# kiwi-basic.net
KiCad netlist of a schematic drawn in EAGLE
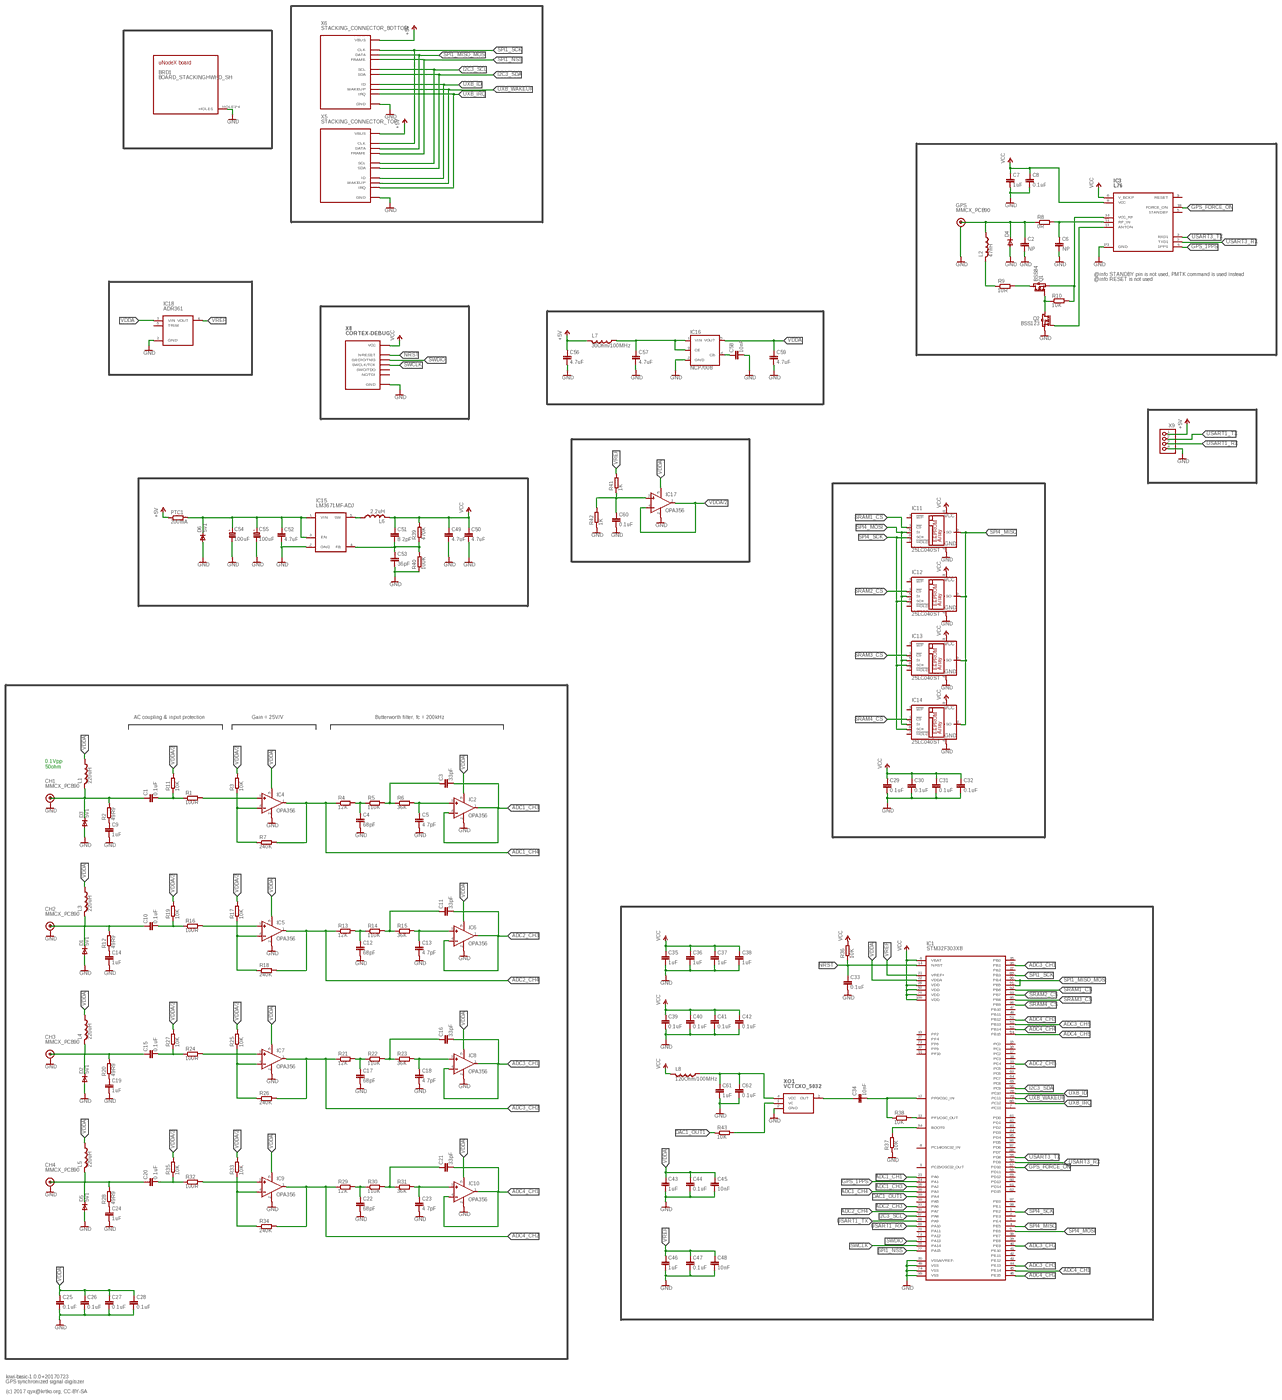
[diagram p0: schematic, sheet 1, overview]
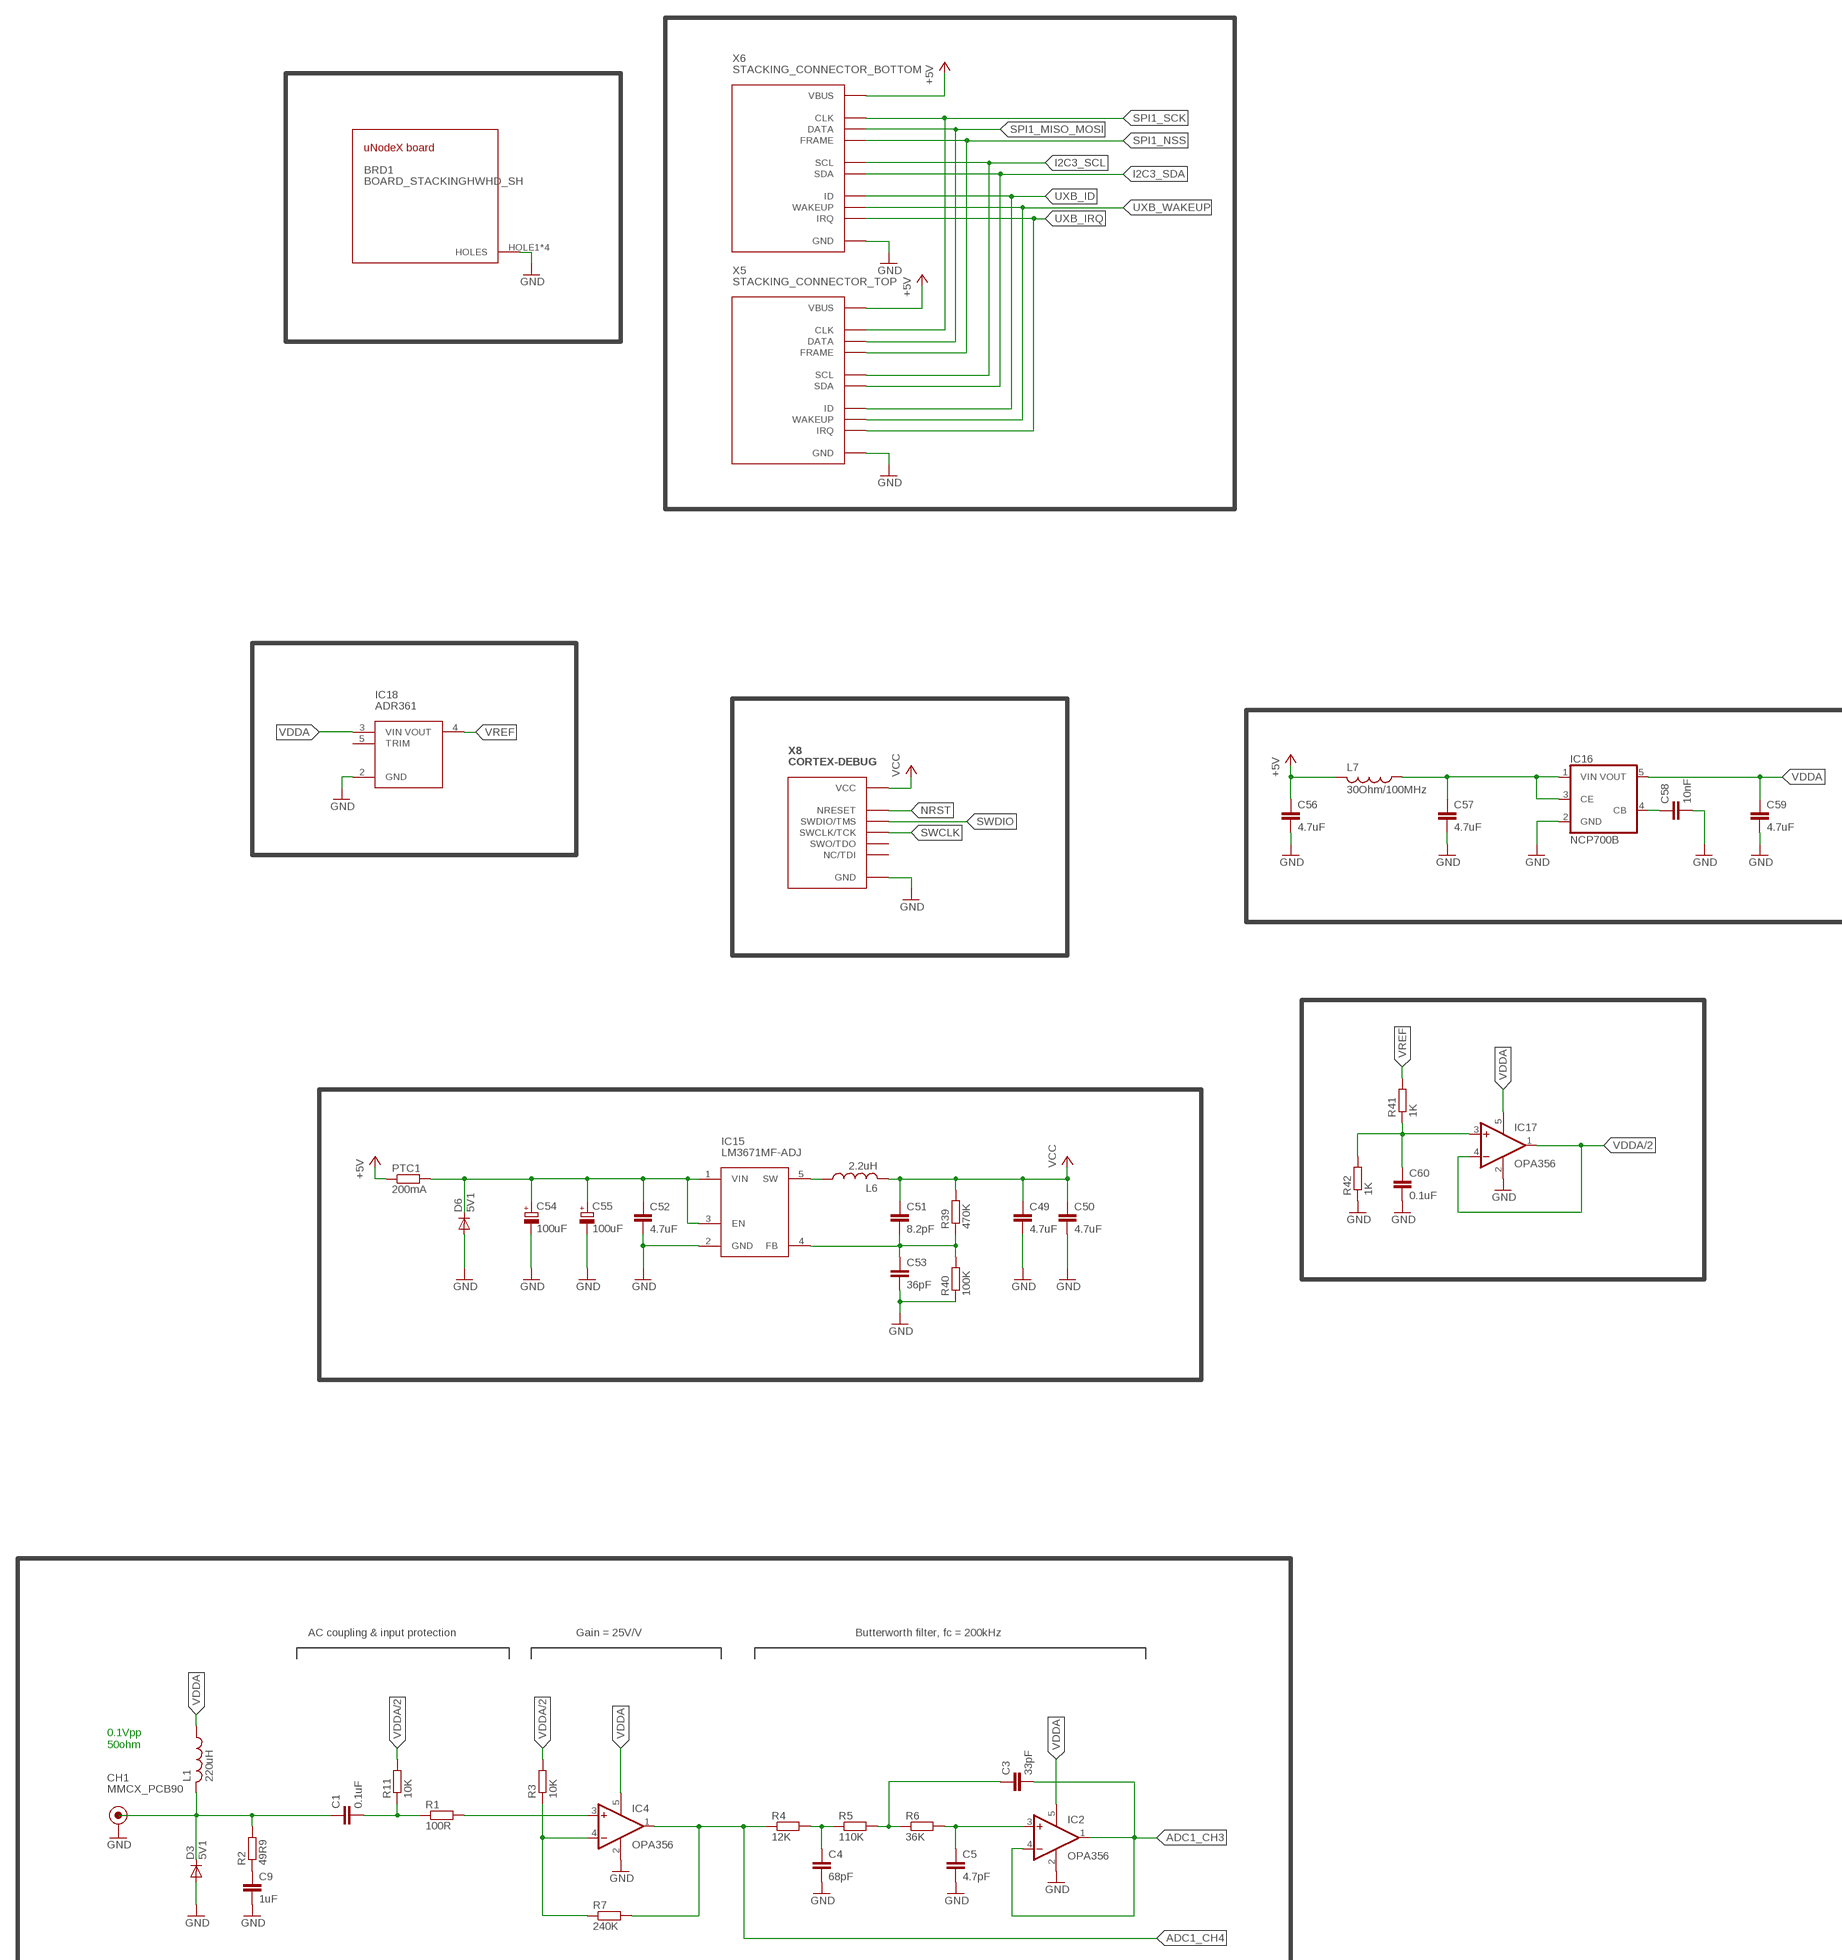
[diagram p1: schematic, sheet 1, part 1 of 4]
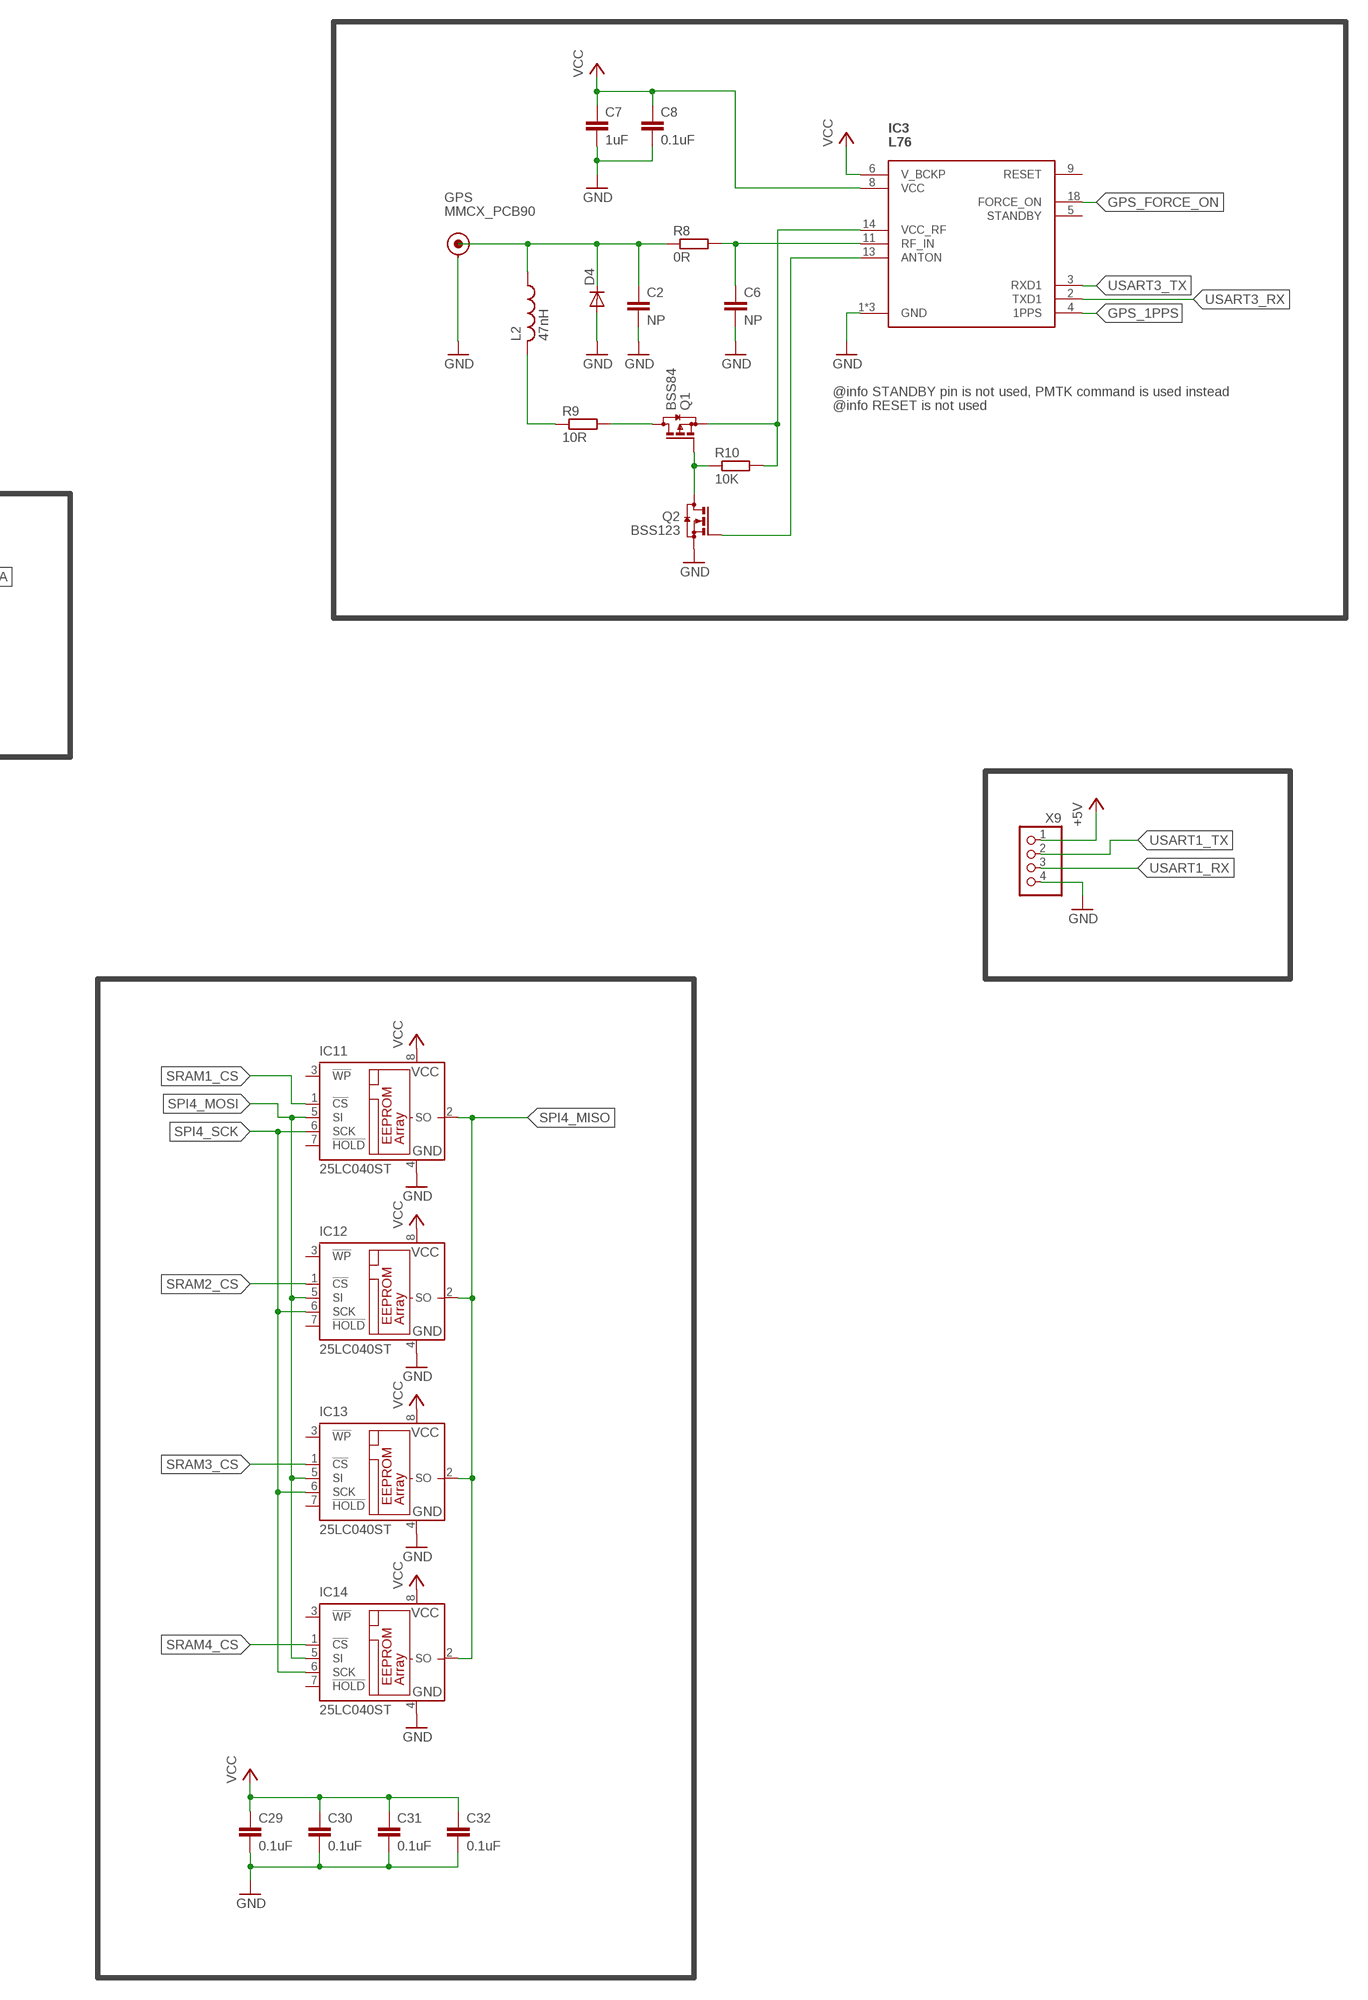
[diagram p2: schematic, sheet 1, part 2 of 4]
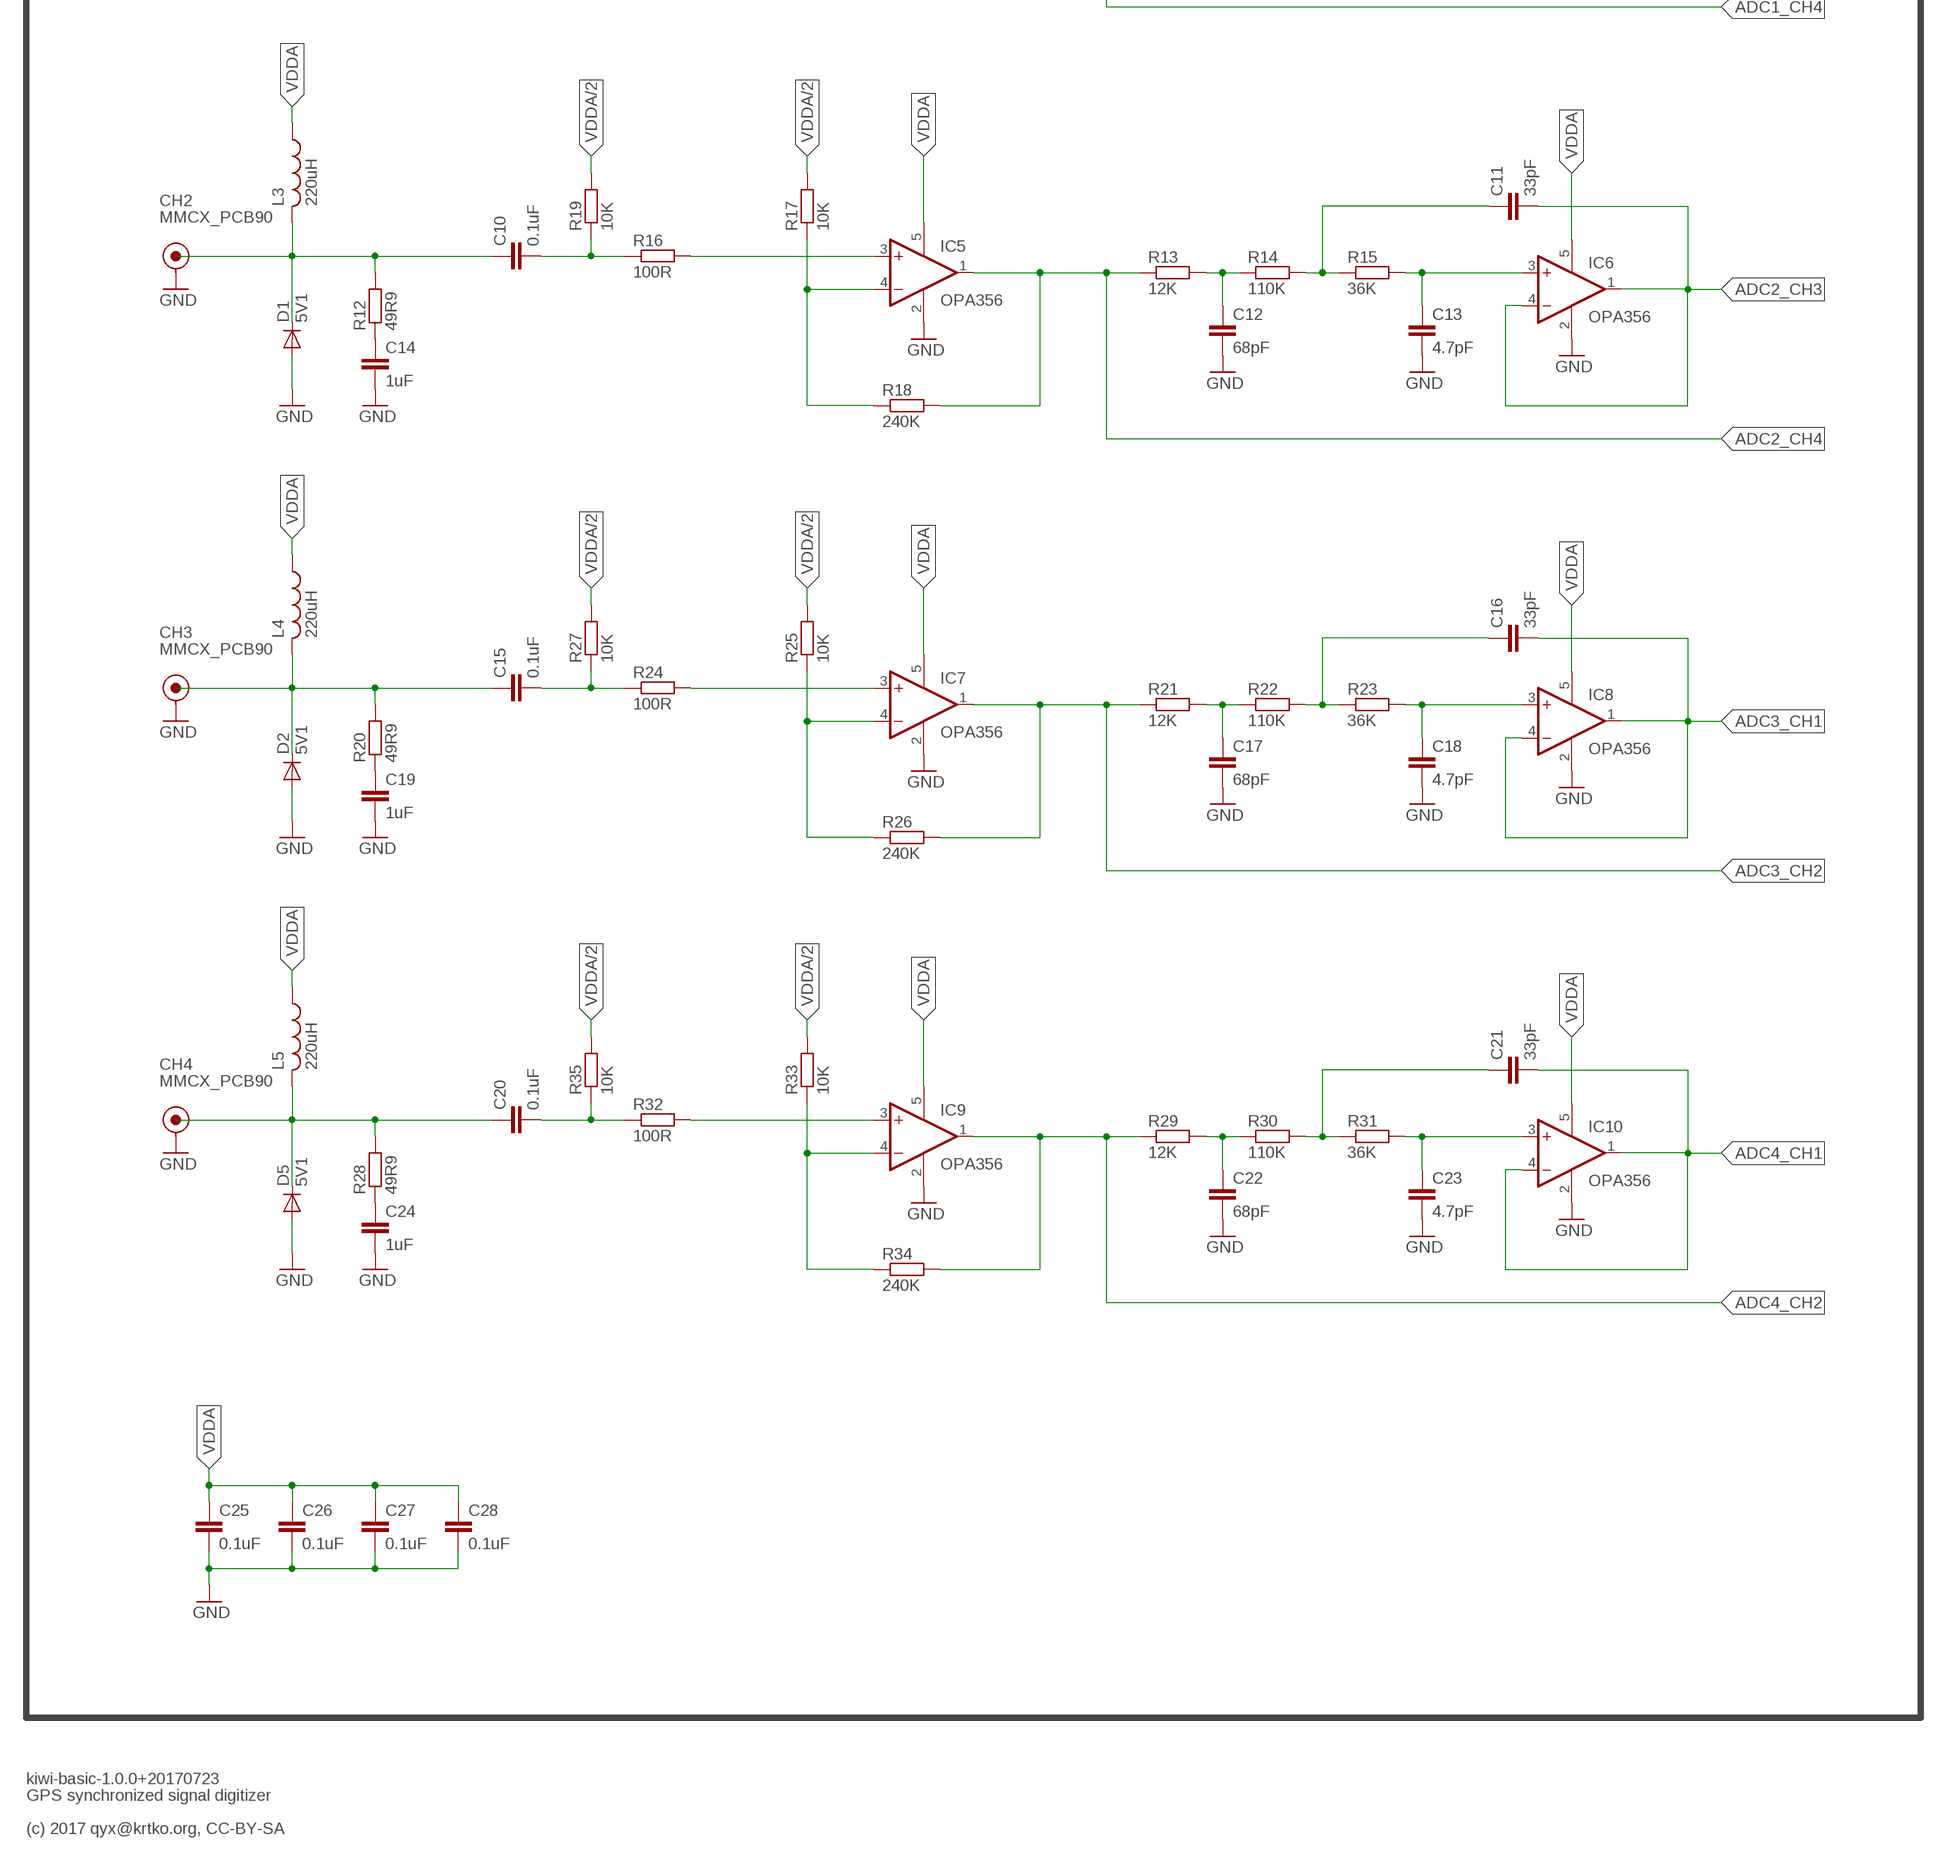
[diagram p3: schematic, sheet 1, part 3 of 4]
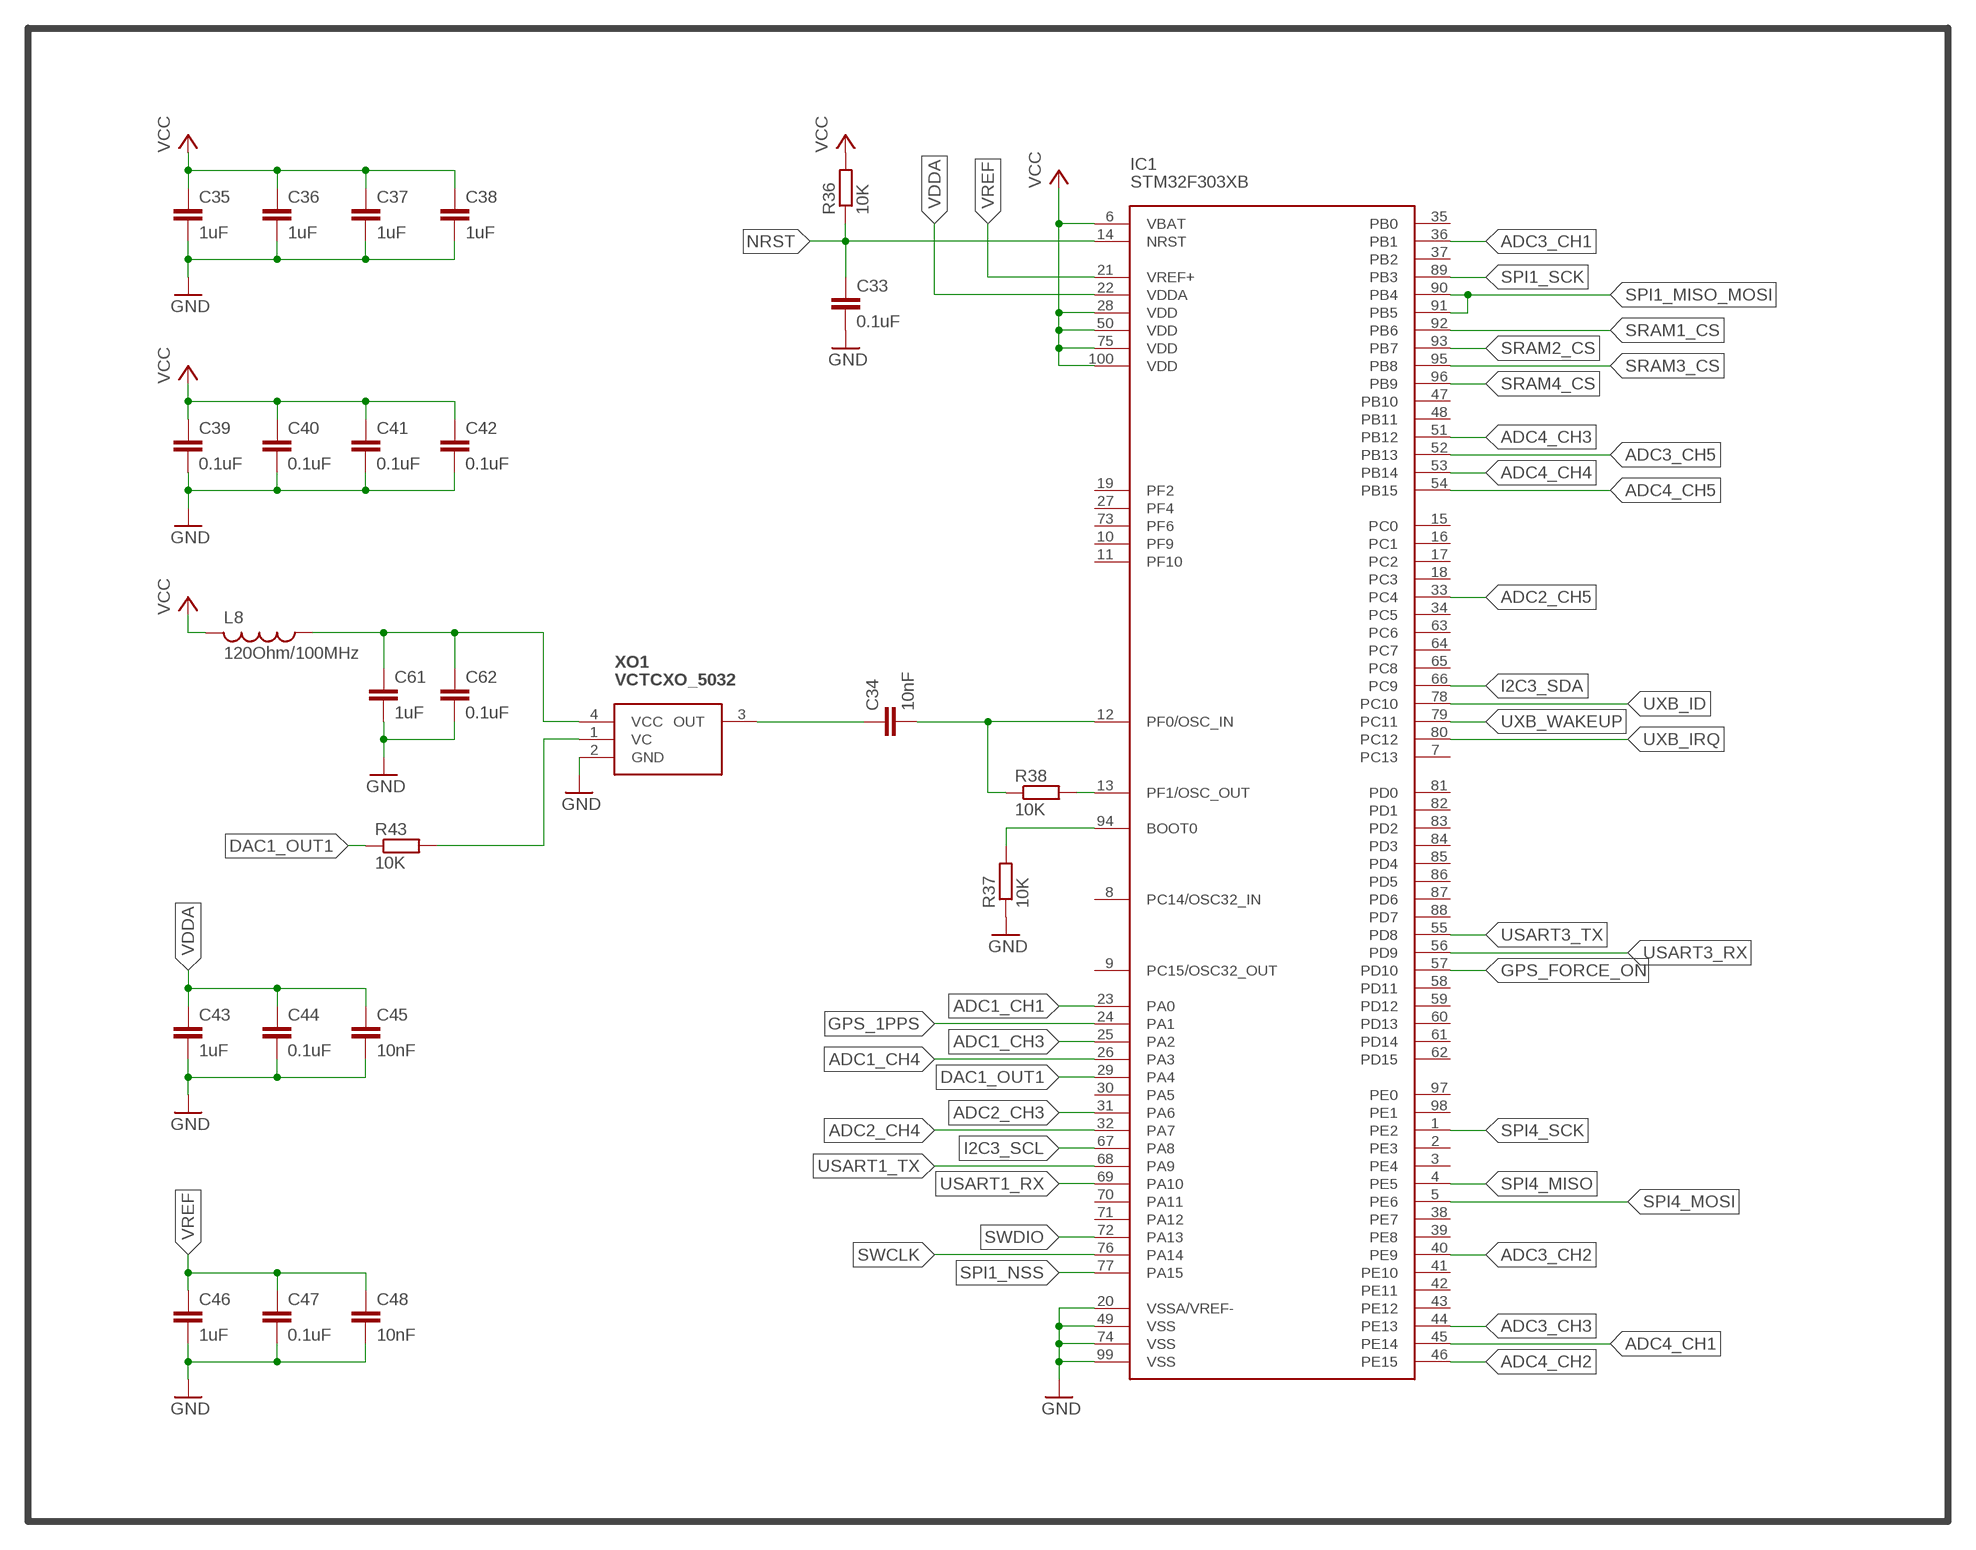
[diagram p4: schematic, sheet 1, part 4 of 4]

(export (version "E")
  (design (tool "Eeschema 10.0.6"))
  (components
    (comp (ref "BRD1")
      (value "BOARD_STACKINGHWHD_SH")
      (footprint "eagle-import:HWHD_SHARP_CORNERS")
      (libsource (lib "eagle-import") (part "BOARD_STACKINGHWHD_SH"))
    )
    (comp (ref "C1")
      (value "0.1uF")
      (footprint "eagle-import:C0603")
      (libsource (lib "eagle-import") (part "C-EUC0603"))
    )
    (comp (ref "C2")
      (value "NP")
      (footprint "eagle-import:C0603")
      (libsource (lib "eagle-import") (part "C-EUC0603"))
    )
    (comp (ref "C3")
      (value "33pF")
      (footprint "eagle-import:C0603")
      (libsource (lib "eagle-import") (part "C-EUC0603"))
    )
    (comp (ref "C4")
      (value "68pF")
      (footprint "eagle-import:C0603")
      (libsource (lib "eagle-import") (part "C-EUC0603"))
    )
    (comp (ref "C5")
      (value "4.7pF")
      (footprint "eagle-import:C0603")
      (libsource (lib "eagle-import") (part "C-EUC0603"))
    )
    (comp (ref "C6")
      (value "NP")
      (footprint "eagle-import:C0603")
      (libsource (lib "eagle-import") (part "C-EUC0603"))
    )
    (comp (ref "C7")
      (value "1uF")
      (footprint "eagle-import:C0603")
      (libsource (lib "eagle-import") (part "C-EUC0603"))
    )
    (comp (ref "C8")
      (value "0.1uF")
      (footprint "eagle-import:C0603")
      (libsource (lib "eagle-import") (part "C-EUC0603"))
    )
    (comp (ref "C9")
      (value "1uF")
      (footprint "eagle-import:C0603")
      (libsource (lib "eagle-import") (part "C-EUC0603"))
    )
    (comp (ref "C10")
      (value "0.1uF")
      (footprint "eagle-import:C0603")
      (libsource (lib "eagle-import") (part "C-EUC0603"))
    )
    (comp (ref "C11")
      (value "33pF")
      (footprint "eagle-import:C0603")
      (libsource (lib "eagle-import") (part "C-EUC0603"))
    )
    (comp (ref "C12")
      (value "68pF")
      (footprint "eagle-import:C0603")
      (libsource (lib "eagle-import") (part "C-EUC0603"))
    )
    (comp (ref "C13")
      (value "4.7pF")
      (footprint "eagle-import:C0603")
      (libsource (lib "eagle-import") (part "C-EUC0603"))
    )
    (comp (ref "C14")
      (value "1uF")
      (footprint "eagle-import:C0603")
      (libsource (lib "eagle-import") (part "C-EUC0603"))
    )
    (comp (ref "C15")
      (value "0.1uF")
      (footprint "eagle-import:C0603")
      (libsource (lib "eagle-import") (part "C-EUC0603"))
    )
    (comp (ref "C16")
      (value "33pF")
      (footprint "eagle-import:C0603")
      (libsource (lib "eagle-import") (part "C-EUC0603"))
    )
    (comp (ref "C17")
      (value "68pF")
      (footprint "eagle-import:C0603")
      (libsource (lib "eagle-import") (part "C-EUC0603"))
    )
    (comp (ref "C18")
      (value "4.7pF")
      (footprint "eagle-import:C0603")
      (libsource (lib "eagle-import") (part "C-EUC0603"))
    )
    (comp (ref "C19")
      (value "1uF")
      (footprint "eagle-import:C0603")
      (libsource (lib "eagle-import") (part "C-EUC0603"))
    )
    (comp (ref "C20")
      (value "0.1uF")
      (footprint "eagle-import:C0603")
      (libsource (lib "eagle-import") (part "C-EUC0603"))
    )
    (comp (ref "C21")
      (value "33pF")
      (footprint "eagle-import:C0603")
      (libsource (lib "eagle-import") (part "C-EUC0603"))
    )
    (comp (ref "C22")
      (value "68pF")
      (footprint "eagle-import:C0603")
      (libsource (lib "eagle-import") (part "C-EUC0603"))
    )
    (comp (ref "C23")
      (value "4.7pF")
      (footprint "eagle-import:C0603")
      (libsource (lib "eagle-import") (part "C-EUC0603"))
    )
    (comp (ref "C24")
      (value "1uF")
      (footprint "eagle-import:C0603")
      (libsource (lib "eagle-import") (part "C-EUC0603"))
    )
    (comp (ref "C25")
      (value "0.1uF")
      (footprint "eagle-import:C0603")
      (libsource (lib "eagle-import") (part "C-EUC0603"))
    )
    (comp (ref "C26")
      (value "0.1uF")
      (footprint "eagle-import:C0603")
      (libsource (lib "eagle-import") (part "C-EUC0603"))
    )
    (comp (ref "C27")
      (value "0.1uF")
      (footprint "eagle-import:C0603")
      (libsource (lib "eagle-import") (part "C-EUC0603"))
    )
    (comp (ref "C28")
      (value "0.1uF")
      (footprint "eagle-import:C0603")
      (libsource (lib "eagle-import") (part "C-EUC0603"))
    )
    (comp (ref "C29")
      (value "0.1uF")
      (footprint "eagle-import:C0603")
      (libsource (lib "eagle-import") (part "C-EUC0603"))
    )
    (comp (ref "C30")
      (value "0.1uF")
      (footprint "eagle-import:C0603")
      (libsource (lib "eagle-import") (part "C-EUC0603"))
    )
    (comp (ref "C31")
      (value "0.1uF")
      (footprint "eagle-import:C0603")
      (libsource (lib "eagle-import") (part "C-EUC0603"))
    )
    (comp (ref "C32")
      (value "0.1uF")
      (footprint "eagle-import:C0603")
      (libsource (lib "eagle-import") (part "C-EUC0603"))
    )
    (comp (ref "C33")
      (value "0.1uF")
      (footprint "eagle-import:C0603")
      (libsource (lib "eagle-import") (part "C-EUC0603"))
    )
    (comp (ref "C34")
      (value "10nF")
      (footprint "eagle-import:C0603")
      (libsource (lib "eagle-import") (part "C-EUC0603"))
    )
    (comp (ref "C35")
      (value "1uF")
      (footprint "eagle-import:C0603")
      (libsource (lib "eagle-import") (part "C-EUC0603"))
    )
    (comp (ref "C36")
      (value "1uF")
      (footprint "eagle-import:C0603")
      (libsource (lib "eagle-import") (part "C-EUC0603"))
    )
    (comp (ref "C37")
      (value "1uF")
      (footprint "eagle-import:C0603")
      (libsource (lib "eagle-import") (part "C-EUC0603"))
    )
    (comp (ref "C38")
      (value "1uF")
      (footprint "eagle-import:C0603")
      (libsource (lib "eagle-import") (part "C-EUC0603"))
    )
    (comp (ref "C39")
      (value "0.1uF")
      (footprint "eagle-import:C0603")
      (libsource (lib "eagle-import") (part "C-EUC0603"))
    )
    (comp (ref "C40")
      (value "0.1uF")
      (footprint "eagle-import:C0603")
      (libsource (lib "eagle-import") (part "C-EUC0603"))
    )
    (comp (ref "C41")
      (value "0.1uF")
      (footprint "eagle-import:C0603")
      (libsource (lib "eagle-import") (part "C-EUC0603"))
    )
    (comp (ref "C42")
      (value "0.1uF")
      (footprint "eagle-import:C0603")
      (libsource (lib "eagle-import") (part "C-EUC0603"))
    )
    (comp (ref "C43")
      (value "1uF")
      (footprint "eagle-import:C0603")
      (libsource (lib "eagle-import") (part "C-EUC0603"))
    )
    (comp (ref "C44")
      (value "0.1uF")
      (footprint "eagle-import:C0603")
      (libsource (lib "eagle-import") (part "C-EUC0603"))
    )
    (comp (ref "C45")
      (value "10nF")
      (footprint "eagle-import:C0603")
      (libsource (lib "eagle-import") (part "C-EUC0603"))
    )
    (comp (ref "C46")
      (value "1uF")
      (footprint "eagle-import:C0603")
      (libsource (lib "eagle-import") (part "C-EUC0603"))
    )
    (comp (ref "C47")
      (value "0.1uF")
      (footprint "eagle-import:C0603")
      (libsource (lib "eagle-import") (part "C-EUC0603"))
    )
    (comp (ref "C48")
      (value "10nF")
      (footprint "eagle-import:C0603")
      (libsource (lib "eagle-import") (part "C-EUC0603"))
    )
    (comp (ref "C49")
      (value "4.7uF")
      (footprint "eagle-import:C0805")
      (libsource (lib "eagle-import") (part "C-EUC0805"))
    )
    (comp (ref "C50")
      (value "4.7uF")
      (footprint "eagle-import:C0805")
      (libsource (lib "eagle-import") (part "C-EUC0805"))
    )
    (comp (ref "C51")
      (value "8.2pF")
      (footprint "eagle-import:C0603")
      (libsource (lib "eagle-import") (part "C-EUC0603"))
    )
    (comp (ref "C52")
      (value "4.7uF")
      (footprint "eagle-import:C0805")
      (libsource (lib "eagle-import") (part "C-EUC0805"))
    )
    (comp (ref "C53")
      (value "36pF")
      (footprint "eagle-import:C0603")
      (libsource (lib "eagle-import") (part "C-EUC0603"))
    )
    (comp (ref "C54")
      (value "100uF")
      (footprint "eagle-import:PANASONIC_D")
      (libsource (lib "eagle-import") (part "CPOL-EUD"))
    )
    (comp (ref "C55")
      (value "100uF")
      (footprint "eagle-import:PANASONIC_D")
      (libsource (lib "eagle-import") (part "CPOL-EUD"))
    )
    (comp (ref "C56")
      (value "4.7uF")
      (footprint "eagle-import:C0805")
      (libsource (lib "eagle-import") (part "C-EUC0805"))
    )
    (comp (ref "C57")
      (value "4.7uF")
      (footprint "eagle-import:C0805")
      (libsource (lib "eagle-import") (part "C-EUC0805"))
    )
    (comp (ref "C58")
      (value "10nF")
      (footprint "eagle-import:C0603")
      (libsource (lib "eagle-import") (part "C-EUC0603"))
    )
    (comp (ref "C59")
      (value "4.7uF")
      (footprint "eagle-import:C0805")
      (libsource (lib "eagle-import") (part "C-EUC0805"))
    )
    (comp (ref "C60")
      (value "0.1uF")
      (footprint "eagle-import:C0603")
      (libsource (lib "eagle-import") (part "C-EUC0603"))
    )
    (comp (ref "C61")
      (value "1uF")
      (footprint "eagle-import:C0603")
      (libsource (lib "eagle-import") (part "C-EUC0603"))
    )
    (comp (ref "C62")
      (value "0.1uF")
      (footprint "eagle-import:C0603")
      (libsource (lib "eagle-import") (part "C-EUC0603"))
    )
    (comp (ref "CH1")
      (value "MMCX_PCB90")
      (footprint "eagle-import:MMCX_PCB_90")
      (libsource (lib "eagle-import") (part "MMCX_PCB90"))
    )
    (comp (ref "CH2")
      (value "MMCX_PCB90")
      (footprint "eagle-import:MMCX_PCB_90")
      (libsource (lib "eagle-import") (part "MMCX_PCB90"))
    )
    (comp (ref "CH3")
      (value "MMCX_PCB90")
      (footprint "eagle-import:MMCX_PCB_90")
      (libsource (lib "eagle-import") (part "MMCX_PCB90"))
    )
    (comp (ref "CH4")
      (value "MMCX_PCB90")
      (footprint "eagle-import:MMCX_PCB_90")
      (libsource (lib "eagle-import") (part "MMCX_PCB90"))
    )
    (comp (ref "D1")
      (value "5V1")
      (footprint "eagle-import:SOD323-W")
      (libsource (lib "eagle-import") (part "DIODE-SOD323-W"))
    )
    (comp (ref "D2")
      (value "5V1")
      (footprint "eagle-import:SOD323-W")
      (libsource (lib "eagle-import") (part "DIODE-SOD323-W"))
    )
    (comp (ref "D3")
      (value "5V1")
      (footprint "eagle-import:SOD323-W")
      (libsource (lib "eagle-import") (part "DIODE-SOD323-W"))
    )
    (comp (ref "D4")
      (value "DIODE-SOD323-W")
      (footprint "eagle-import:SOD323-W")
      (libsource (lib "eagle-import") (part "DIODE-SOD323-W"))
    )
    (comp (ref "D5")
      (value "5V1")
      (footprint "eagle-import:SOD323-W")
      (libsource (lib "eagle-import") (part "DIODE-SOD323-W"))
    )
    (comp (ref "D6")
      (value "5V1")
      (footprint "eagle-import:SOD323-W")
      (libsource (lib "eagle-import") (part "DIODE-SOD323-W"))
    )
    (comp (ref "GPS")
      (value "MMCX_PCB90")
      (footprint "eagle-import:MMCX_PCB_90")
      (libsource (lib "eagle-import") (part "MMCX_PCB90"))
    )
    (comp (ref "IC1")
      (value "STM32F303XB")
      (footprint "eagle-import:TQFP100")
      (libsource (lib "eagle-import") (part "STM32F303XB"))
    )
    (comp (ref "IC2")
      (value "OPA356")
      (footprint "eagle-import:SOT23-5")
      (libsource (lib "eagle-import") (part "MCP601OT"))
    )
    (comp (ref "IC3")
      (value "L76")
      (footprint "eagle-import:L76")
      (libsource (lib "eagle-import") (part "L76"))
    )
    (comp (ref "IC4")
      (value "OPA356")
      (footprint "eagle-import:SOT23-5")
      (libsource (lib "eagle-import") (part "MCP601OT"))
    )
    (comp (ref "IC5")
      (value "OPA356")
      (footprint "eagle-import:SOT23-5")
      (libsource (lib "eagle-import") (part "MCP601OT"))
    )
    (comp (ref "IC6")
      (value "OPA356")
      (footprint "eagle-import:SOT23-5")
      (libsource (lib "eagle-import") (part "MCP601OT"))
    )
    (comp (ref "IC7")
      (value "OPA356")
      (footprint "eagle-import:SOT23-5")
      (libsource (lib "eagle-import") (part "MCP601OT"))
    )
    (comp (ref "IC8")
      (value "OPA356")
      (footprint "eagle-import:SOT23-5")
      (libsource (lib "eagle-import") (part "MCP601OT"))
    )
    (comp (ref "IC9")
      (value "OPA356")
      (footprint "eagle-import:SOT23-5")
      (libsource (lib "eagle-import") (part "MCP601OT"))
    )
    (comp (ref "IC10")
      (value "OPA356")
      (footprint "eagle-import:SOT23-5")
      (libsource (lib "eagle-import") (part "MCP601OT"))
    )
    (comp (ref "IC11")
      (value "25LC040ST")
      (footprint "eagle-import:TSSOP8")
      (fields (field (name "MF") "MICROCHIP") (field (name "MPN") "25LC040A-I/ST"))
      (libsource (lib "eagle-import") (part "25STLC040"))
    )
    (comp (ref "IC12")
      (value "25LC040ST")
      (footprint "eagle-import:TSSOP8")
      (fields (field (name "MF") "MICROCHIP") (field (name "MPN") "25LC040A-I/ST"))
      (libsource (lib "eagle-import") (part "25STLC040"))
    )
    (comp (ref "IC13")
      (value "25LC040ST")
      (footprint "eagle-import:TSSOP8")
      (fields (field (name "MF") "MICROCHIP") (field (name "MPN") "25LC040A-I/ST"))
      (libsource (lib "eagle-import") (part "25STLC040"))
    )
    (comp (ref "IC14")
      (value "25LC040ST")
      (footprint "eagle-import:TSSOP8")
      (fields (field (name "MF") "MICROCHIP") (field (name "MPN") "25LC040A-I/ST"))
      (libsource (lib "eagle-import") (part "25STLC040"))
    )
    (comp (ref "IC15")
      (value "LM3671MF-ADJ")
      (footprint "eagle-import:SOT23-5")
      (libsource (lib "eagle-import") (part "LM3671MF"))
    )
    (comp (ref "IC16")
      (value "NCP700B")
      (footprint "eagle-import:SOT25")
      (libsource (lib "eagle-import") (part "TS520530"))
    )
    (comp (ref "IC17")
      (value "OPA356")
      (footprint "eagle-import:SOT23-5")
      (libsource (lib "eagle-import") (part "MCP601OT"))
    )
    (comp (ref "IC18")
      (value "ADR361")
      (footprint "eagle-import:SOT23-5")
      (libsource (lib "eagle-import") (part "ADR361"))
    )
    (comp (ref "L1")
      (value "220uH")
      (footprint "eagle-import:L2012C")
      (libsource (lib "eagle-import") (part "L-USL2012C"))
    )
    (comp (ref "L2")
      (value "47nH")
      (footprint "eagle-import:L2012C")
      (libsource (lib "eagle-import") (part "L-USL2012C"))
    )
    (comp (ref "L3")
      (value "220uH")
      (footprint "eagle-import:L2012C")
      (libsource (lib "eagle-import") (part "L-USL2012C"))
    )
    (comp (ref "L4")
      (value "220uH")
      (footprint "eagle-import:L2012C")
      (libsource (lib "eagle-import") (part "L-USL2012C"))
    )
    (comp (ref "L5")
      (value "220uH")
      (footprint "eagle-import:L2012C")
      (libsource (lib "eagle-import") (part "L-USL2012C"))
    )
    (comp (ref "L6")
      (value "2.2uH")
      (footprint "eagle-import:L2825P")
      (libsource (lib "eagle-import") (part "L-USL2825P"))
    )
    (comp (ref "L7")
      (value "30Ohm/100MHz")
      (footprint "eagle-import:L2012C")
      (libsource (lib "eagle-import") (part "L-USL2012C"))
    )
    (comp (ref "L8")
      (value "120Ohm/100MHz")
      (footprint "eagle-import:L2012C")
      (libsource (lib "eagle-import") (part "L-USL2012C"))
    )
    (comp (ref "PTC1")
      (value "200mA")
      (footprint "eagle-import:R1206")
      (libsource (lib "eagle-import") (part "R-EU_R1206"))
    )
    (comp (ref "Q1")
      (value "BSS84")
      (footprint "eagle-import:SOT23")
      (libsource (lib "eagle-import") (part "BSS84"))
    )
    (comp (ref "Q2")
      (value "BSS123")
      (footprint "eagle-import:SOT23")
      (libsource (lib "eagle-import") (part "BSS123"))
    )
    (comp (ref "R1")
      (value "100R")
      (footprint "eagle-import:R0603")
      (libsource (lib "eagle-import") (part "R-EU_R0603"))
    )
    (comp (ref "R2")
      (value "49R9")
      (footprint "eagle-import:R0603")
      (libsource (lib "eagle-import") (part "R-EU_R0603"))
    )
    (comp (ref "R3")
      (value "10K")
      (footprint "eagle-import:R0603")
      (libsource (lib "eagle-import") (part "R-EU_R0603"))
    )
    (comp (ref "R4")
      (value "12K")
      (footprint "eagle-import:R0603")
      (libsource (lib "eagle-import") (part "R-EU_R0603"))
    )
    (comp (ref "R5")
      (value "110K")
      (footprint "eagle-import:R0603")
      (libsource (lib "eagle-import") (part "R-EU_R0603"))
    )
    (comp (ref "R6")
      (value "36K")
      (footprint "eagle-import:R0603")
      (libsource (lib "eagle-import") (part "R-EU_R0603"))
    )
    (comp (ref "R7")
      (value "240K")
      (footprint "eagle-import:R0603")
      (libsource (lib "eagle-import") (part "R-EU_R0603"))
    )
    (comp (ref "R8")
      (value "0R")
      (footprint "eagle-import:R0603")
      (libsource (lib "eagle-import") (part "R-EU_R0603"))
    )
    (comp (ref "R9")
      (value "10R")
      (footprint "eagle-import:R0603")
      (libsource (lib "eagle-import") (part "R-EU_R0603"))
    )
    (comp (ref "R10")
      (value "10K")
      (footprint "eagle-import:R0603")
      (libsource (lib "eagle-import") (part "R-EU_R0603"))
    )
    (comp (ref "R11")
      (value "10K")
      (footprint "eagle-import:R0603")
      (libsource (lib "eagle-import") (part "R-EU_R0603"))
    )
    (comp (ref "R12")
      (value "49R9")
      (footprint "eagle-import:R0603")
      (libsource (lib "eagle-import") (part "R-EU_R0603"))
    )
    (comp (ref "R13")
      (value "12K")
      (footprint "eagle-import:R0603")
      (libsource (lib "eagle-import") (part "R-EU_R0603"))
    )
    (comp (ref "R14")
      (value "110K")
      (footprint "eagle-import:R0603")
      (libsource (lib "eagle-import") (part "R-EU_R0603"))
    )
    (comp (ref "R15")
      (value "36K")
      (footprint "eagle-import:R0603")
      (libsource (lib "eagle-import") (part "R-EU_R0603"))
    )
    (comp (ref "R16")
      (value "100R")
      (footprint "eagle-import:R0603")
      (libsource (lib "eagle-import") (part "R-EU_R0603"))
    )
    (comp (ref "R17")
      (value "10K")
      (footprint "eagle-import:R0603")
      (libsource (lib "eagle-import") (part "R-EU_R0603"))
    )
    (comp (ref "R18")
      (value "240K")
      (footprint "eagle-import:R0603")
      (libsource (lib "eagle-import") (part "R-EU_R0603"))
    )
    (comp (ref "R19")
      (value "10K")
      (footprint "eagle-import:R0603")
      (libsource (lib "eagle-import") (part "R-EU_R0603"))
    )
    (comp (ref "R20")
      (value "49R9")
      (footprint "eagle-import:R0603")
      (libsource (lib "eagle-import") (part "R-EU_R0603"))
    )
    (comp (ref "R21")
      (value "12K")
      (footprint "eagle-import:R0603")
      (libsource (lib "eagle-import") (part "R-EU_R0603"))
    )
    (comp (ref "R22")
      (value "110K")
      (footprint "eagle-import:R0603")
      (libsource (lib "eagle-import") (part "R-EU_R0603"))
    )
    (comp (ref "R23")
      (value "36K")
      (footprint "eagle-import:R0603")
      (libsource (lib "eagle-import") (part "R-EU_R0603"))
    )
    (comp (ref "R24")
      (value "100R")
      (footprint "eagle-import:R0603")
      (libsource (lib "eagle-import") (part "R-EU_R0603"))
    )
    (comp (ref "R25")
      (value "10K")
      (footprint "eagle-import:R0603")
      (libsource (lib "eagle-import") (part "R-EU_R0603"))
    )
    (comp (ref "R26")
      (value "240K")
      (footprint "eagle-import:R0603")
      (libsource (lib "eagle-import") (part "R-EU_R0603"))
    )
    (comp (ref "R27")
      (value "10K")
      (footprint "eagle-import:R0603")
      (libsource (lib "eagle-import") (part "R-EU_R0603"))
    )
    (comp (ref "R28")
      (value "49R9")
      (footprint "eagle-import:R0603")
      (libsource (lib "eagle-import") (part "R-EU_R0603"))
    )
    (comp (ref "R29")
      (value "12K")
      (footprint "eagle-import:R0603")
      (libsource (lib "eagle-import") (part "R-EU_R0603"))
    )
    (comp (ref "R30")
      (value "110K")
      (footprint "eagle-import:R0603")
      (libsource (lib "eagle-import") (part "R-EU_R0603"))
    )
    (comp (ref "R31")
      (value "36K")
      (footprint "eagle-import:R0603")
      (libsource (lib "eagle-import") (part "R-EU_R0603"))
    )
    (comp (ref "R32")
      (value "100R")
      (footprint "eagle-import:R0603")
      (libsource (lib "eagle-import") (part "R-EU_R0603"))
    )
    (comp (ref "R33")
      (value "10K")
      (footprint "eagle-import:R0603")
      (libsource (lib "eagle-import") (part "R-EU_R0603"))
    )
    (comp (ref "R34")
      (value "240K")
      (footprint "eagle-import:R0603")
      (libsource (lib "eagle-import") (part "R-EU_R0603"))
    )
    (comp (ref "R35")
      (value "10K")
      (footprint "eagle-import:R0603")
      (libsource (lib "eagle-import") (part "R-EU_R0603"))
    )
    (comp (ref "R36")
      (value "10K")
      (footprint "eagle-import:R0603")
      (libsource (lib "eagle-import") (part "R-EU_R0603"))
    )
    (comp (ref "R37")
      (value "10K")
      (footprint "eagle-import:R0603")
      (libsource (lib "eagle-import") (part "R-EU_R0603"))
    )
    (comp (ref "R38")
      (value "10K")
      (footprint "eagle-import:R0603")
      (libsource (lib "eagle-import") (part "R-EU_R0603"))
    )
    (comp (ref "R39")
      (value "470K")
      (footprint "eagle-import:R0603")
      (libsource (lib "eagle-import") (part "R-EU_R0603"))
    )
    (comp (ref "R40")
      (value "100K")
      (footprint "eagle-import:R0603")
      (libsource (lib "eagle-import") (part "R-EU_R0603"))
    )
    (comp (ref "R41")
      (value "1K")
      (footprint "eagle-import:R0603")
      (libsource (lib "eagle-import") (part "R-EU_R0603"))
    )
    (comp (ref "R42")
      (value "1K")
      (footprint "eagle-import:R0603")
      (libsource (lib "eagle-import") (part "R-EU_R0603"))
    )
    (comp (ref "R43")
      (value "10K")
      (footprint "eagle-import:R0603")
      (libsource (lib "eagle-import") (part "R-EU_R0603"))
    )
    (comp (ref "X5")
      (value "STACKING_CONNECTOR_TOP")
      (footprint "eagle-import:HAR-FLEX-TOP-12P")
      (libsource (lib "eagle-import") (part "STACKING_CONNECTOR_TOP"))
    )
    (comp (ref "X6")
      (value "STACKING_CONNECTOR_BOTTOM")
      (footprint "eagle-import:HAR-FLEX-BOTTOM-12P")
      (libsource (lib "eagle-import") (part "STACKING_CONNECTOR_BOTTOM"))
    )
    (comp (ref "X8")
      (value "CORTEX-DEBUG")
      (footprint "eagle-import:CORTEX-DEBUG")
      (libsource (lib "eagle-import") (part "CORTEX-DEBUG"))
    )
    (comp (ref "X9")
      (value "PINHD-1X4")
      (footprint "eagle-import:1X04")
      (libsource (lib "eagle-import") (part "PINHD-1X4"))
    )
    (comp (ref "XO1")
      (value "VCTCXO_5032")
      (footprint "eagle-import:XTAL_5032")
      (libsource (lib "eagle-import") (part "VCTCXO_5032"))
    )
  )
  (nets
    (net (code "1") (name "+5V") (class "Default")
      (node (ref "C56") (pin "1") (pinfunction "1_1") (pintype "passive"))
      (node (ref "L7") (pin "2") (pinfunction "2_2") (pintype "passive"))
      (node (ref "PTC1") (pin "1") (pinfunction "1_1") (pintype "passive"))
      (node (ref "X5") (pin "VBUS") (pinfunction "VBUS_VBUS") (pintype "bidirectional"))
      (node (ref "X6") (pin "VBUS") (pinfunction "VBUS_VBUS") (pintype "bidirectional"))
      (node (ref "X9") (pin "1") (pinfunction "1_1") (pintype "passive"))
    )
    (net (code "2") (name "ADC1_CH1") (class "Default")
      (node (ref "IC1") (pin "23") (pinfunction "PA0_23") (pintype "bidirectional"))
    )
    (net (code "3") (name "ADC1_CH3") (class "Default")
      (node (ref "C3") (pin "2") (pinfunction "2_2") (pintype "passive"))
      (node (ref "IC1") (pin "25") (pinfunction "PA2_25") (pintype "bidirectional"))
      (node (ref "IC2") (pin "1") (pinfunction "OUT_1") (pintype "output"))
      (node (ref "IC2") (pin "4") (pinfunction "-IN_4") (pintype "input"))
    )
    (net (code "4") (name "ADC1_CH4") (class "Default")
      (node (ref "IC1") (pin "26") (pinfunction "PA3_26") (pintype "bidirectional"))
      (node (ref "IC4") (pin "1") (pinfunction "OUT_1") (pintype "output"))
      (node (ref "R4") (pin "1") (pinfunction "1_1") (pintype "passive"))
      (node (ref "R7") (pin "2") (pinfunction "2_2") (pintype "passive"))
    )
    (net (code "5") (name "ADC2_CH3") (class "Default")
      (node (ref "C11") (pin "2") (pinfunction "2_2") (pintype "passive"))
      (node (ref "IC1") (pin "31") (pinfunction "PA6_31") (pintype "bidirectional"))
      (node (ref "IC6") (pin "1") (pinfunction "OUT_1") (pintype "output"))
      (node (ref "IC6") (pin "4") (pinfunction "-IN_4") (pintype "input"))
    )
    (net (code "6") (name "ADC2_CH4") (class "Default")
      (node (ref "IC1") (pin "32") (pinfunction "PA7_32") (pintype "bidirectional"))
      (node (ref "IC5") (pin "1") (pinfunction "OUT_1") (pintype "output"))
      (node (ref "R13") (pin "1") (pinfunction "1_1") (pintype "passive"))
      (node (ref "R18") (pin "2") (pinfunction "2_2") (pintype "passive"))
    )
    (net (code "7") (name "ADC2_CH5") (class "Default")
      (node (ref "IC1") (pin "33") (pinfunction "PC4_33") (pintype "bidirectional"))
    )
    (net (code "8") (name "ADC3_CH1") (class "Default")
      (node (ref "C16") (pin "2") (pinfunction "2_2") (pintype "passive"))
      (node (ref "IC1") (pin "36") (pinfunction "PB1_36") (pintype "bidirectional"))
      (node (ref "IC8") (pin "1") (pinfunction "OUT_1") (pintype "output"))
      (node (ref "IC8") (pin "4") (pinfunction "-IN_4") (pintype "input"))
    )
    (net (code "9") (name "ADC3_CH2") (class "Default")
      (node (ref "IC1") (pin "40") (pinfunction "PE9_40") (pintype "bidirectional"))
      (node (ref "IC7") (pin "1") (pinfunction "OUT_1") (pintype "output"))
      (node (ref "R21") (pin "1") (pinfunction "1_1") (pintype "passive"))
      (node (ref "R26") (pin "2") (pinfunction "2_2") (pintype "passive"))
    )
    (net (code "10") (name "ADC3_CH3") (class "Default")
      (node (ref "IC1") (pin "44") (pinfunction "PE13_44") (pintype "bidirectional"))
    )
    (net (code "11") (name "ADC3_CH5") (class "Default")
      (node (ref "IC1") (pin "52") (pinfunction "PB13_52") (pintype "bidirectional"))
    )
    (net (code "12") (name "ADC4_CH1") (class "Default")
      (node (ref "C21") (pin "2") (pinfunction "2_2") (pintype "passive"))
      (node (ref "IC1") (pin "45") (pinfunction "PE14_45") (pintype "bidirectional"))
      (node (ref "IC10") (pin "1") (pinfunction "OUT_1") (pintype "output"))
      (node (ref "IC10") (pin "4") (pinfunction "-IN_4") (pintype "input"))
    )
    (net (code "13") (name "ADC4_CH2") (class "Default")
      (node (ref "IC1") (pin "46") (pinfunction "PE15_46") (pintype "bidirectional"))
      (node (ref "IC9") (pin "1") (pinfunction "OUT_1") (pintype "output"))
      (node (ref "R29") (pin "1") (pinfunction "1_1") (pintype "passive"))
      (node (ref "R34") (pin "2") (pinfunction "2_2") (pintype "passive"))
    )
    (net (code "14") (name "ADC4_CH3") (class "Default")
      (node (ref "IC1") (pin "51") (pinfunction "PB12_51") (pintype "bidirectional"))
    )
    (net (code "15") (name "ADC4_CH4") (class "Default")
      (node (ref "IC1") (pin "53") (pinfunction "PB14_53") (pintype "bidirectional"))
    )
    (net (code "16") (name "ADC4_CH5") (class "Default")
      (node (ref "IC1") (pin "54") (pinfunction "PB15_54") (pintype "bidirectional"))
    )
    (net (code "17") (name "DAC1_OUT1") (class "Default")
      (node (ref "IC1") (pin "29") (pinfunction "PA4_29") (pintype "bidirectional"))
      (node (ref "R43") (pin "1") (pinfunction "1_1") (pintype "passive"))
    )
    (net (code "18") (name "GND") (class "Default")
      (node (ref "BRD1") (pin "HOLE1") (pinfunction "HOLES_HOLE1") (pintype "bidirectional"))
      (node (ref "BRD1") (pin "HOLE2") (pinfunction "HOLES_HOLE2") (pintype "bidirectional"))
      (node (ref "BRD1") (pin "HOLE3") (pinfunction "HOLES_HOLE3") (pintype "bidirectional"))
      (node (ref "BRD1") (pin "HOLE4") (pinfunction "HOLES_HOLE4") (pintype "bidirectional"))
      (node (ref "C12") (pin "2") (pinfunction "2_2") (pintype "passive"))
      (node (ref "C13") (pin "2") (pinfunction "2_2") (pintype "passive"))
      (node (ref "C14") (pin "2") (pinfunction "2_2") (pintype "passive"))
      (node (ref "C17") (pin "2") (pinfunction "2_2") (pintype "passive"))
      (node (ref "C18") (pin "2") (pinfunction "2_2") (pintype "passive"))
      (node (ref "C19") (pin "2") (pinfunction "2_2") (pintype "passive"))
      (node (ref "C2") (pin "2") (pinfunction "2_2") (pintype "passive"))
      (node (ref "C22") (pin "2") (pinfunction "2_2") (pintype "passive"))
      (node (ref "C23") (pin "2") (pinfunction "2_2") (pintype "passive"))
      (node (ref "C24") (pin "2") (pinfunction "2_2") (pintype "passive"))
      (node (ref "C25") (pin "2") (pinfunction "2_2") (pintype "passive"))
      (node (ref "C26") (pin "2") (pinfunction "2_2") (pintype "passive"))
      (node (ref "C27") (pin "2") (pinfunction "2_2") (pintype "passive"))
      (node (ref "C28") (pin "2") (pinfunction "2_2") (pintype "passive"))
      (node (ref "C29") (pin "2") (pinfunction "2_2") (pintype "passive"))
      (node (ref "C30") (pin "2") (pinfunction "2_2") (pintype "passive"))
      (node (ref "C31") (pin "2") (pinfunction "2_2") (pintype "passive"))
      (node (ref "C32") (pin "2") (pinfunction "2_2") (pintype "passive"))
      (node (ref "C33") (pin "2") (pinfunction "2_2") (pintype "passive"))
      (node (ref "C35") (pin "2") (pinfunction "2_2") (pintype "passive"))
      (node (ref "C36") (pin "2") (pinfunction "2_2") (pintype "passive"))
      (node (ref "C37") (pin "2") (pinfunction "2_2") (pintype "passive"))
      (node (ref "C38") (pin "2") (pinfunction "2_2") (pintype "passive"))
      (node (ref "C39") (pin "2") (pinfunction "2_2") (pintype "passive"))
      (node (ref "C4") (pin "2") (pinfunction "2_2") (pintype "passive"))
      (node (ref "C40") (pin "2") (pinfunction "2_2") (pintype "passive"))
      (node (ref "C41") (pin "2") (pinfunction "2_2") (pintype "passive"))
      (node (ref "C42") (pin "2") (pinfunction "2_2") (pintype "passive"))
      (node (ref "C43") (pin "2") (pinfunction "2_2") (pintype "passive"))
      (node (ref "C44") (pin "2") (pinfunction "2_2") (pintype "passive"))
      (node (ref "C45") (pin "2") (pinfunction "2_2") (pintype "passive"))
      (node (ref "C46") (pin "2") (pinfunction "2_2") (pintype "passive"))
      (node (ref "C47") (pin "2") (pinfunction "2_2") (pintype "passive"))
      (node (ref "C48") (pin "2") (pinfunction "2_2") (pintype "passive"))
      (node (ref "C49") (pin "2") (pinfunction "2_2") (pintype "passive"))
      (node (ref "C5") (pin "2") (pinfunction "2_2") (pintype "passive"))
      (node (ref "C50") (pin "2") (pinfunction "2_2") (pintype "passive"))
      (node (ref "C52") (pin "2") (pinfunction "2_2") (pintype "passive"))
      (node (ref "C53") (pin "2") (pinfunction "2_2") (pintype "passive"))
      (node (ref "C54") (pin "-") (pinfunction "-_-") (pintype "passive"))
      (node (ref "C55") (pin "-") (pinfunction "-_-") (pintype "passive"))
      (node (ref "C56") (pin "2") (pinfunction "2_2") (pintype "passive"))
      (node (ref "C57") (pin "2") (pinfunction "2_2") (pintype "passive"))
      (node (ref "C58") (pin "2") (pinfunction "2_2") (pintype "passive"))
      (node (ref "C59") (pin "2") (pinfunction "2_2") (pintype "passive"))
      (node (ref "C6") (pin "2") (pinfunction "2_2") (pintype "passive"))
      (node (ref "C60") (pin "2") (pinfunction "2_2") (pintype "passive"))
      (node (ref "C61") (pin "2") (pinfunction "2_2") (pintype "passive"))
      (node (ref "C62") (pin "2") (pinfunction "2_2") (pintype "passive"))
      (node (ref "C7") (pin "2") (pinfunction "2_2") (pintype "passive"))
      (node (ref "C8") (pin "2") (pinfunction "2_2") (pintype "passive"))
      (node (ref "C9") (pin "2") (pinfunction "2_2") (pintype "passive"))
      (node (ref "CH1") (pin "S1") (pinfunction "SHIELD_S1") (pintype "bidirectional"))
      (node (ref "CH1") (pin "S2") (pinfunction "SHIELD_S2") (pintype "bidirectional"))
      (node (ref "CH1") (pin "S3") (pinfunction "SHIELD_S3") (pintype "bidirectional"))
      (node (ref "CH1") (pin "S4") (pinfunction "SHIELD_S4") (pintype "bidirectional"))
      (node (ref "CH2") (pin "S1") (pinfunction "SHIELD_S1") (pintype "bidirectional"))
      (node (ref "CH2") (pin "S2") (pinfunction "SHIELD_S2") (pintype "bidirectional"))
      (node (ref "CH2") (pin "S3") (pinfunction "SHIELD_S3") (pintype "bidirectional"))
      (node (ref "CH2") (pin "S4") (pinfunction "SHIELD_S4") (pintype "bidirectional"))
      (node (ref "CH3") (pin "S1") (pinfunction "SHIELD_S1") (pintype "bidirectional"))
      (node (ref "CH3") (pin "S2") (pinfunction "SHIELD_S2") (pintype "bidirectional"))
      (node (ref "CH3") (pin "S3") (pinfunction "SHIELD_S3") (pintype "bidirectional"))
      (node (ref "CH3") (pin "S4") (pinfunction "SHIELD_S4") (pintype "bidirectional"))
      (node (ref "CH4") (pin "S1") (pinfunction "SHIELD_S1") (pintype "bidirectional"))
      (node (ref "CH4") (pin "S2") (pinfunction "SHIELD_S2") (pintype "bidirectional"))
      (node (ref "CH4") (pin "S3") (pinfunction "SHIELD_S3") (pintype "bidirectional"))
      (node (ref "CH4") (pin "S4") (pinfunction "SHIELD_S4") (pintype "bidirectional"))
      (node (ref "D1") (pin "A") (pinfunction "A_A") (pintype "passive"))
      (node (ref "D2") (pin "A") (pinfunction "A_A") (pintype "passive"))
      (node (ref "D3") (pin "A") (pinfunction "A_A") (pintype "passive"))
      (node (ref "D4") (pin "A") (pinfunction "A_A") (pintype "passive"))
      (node (ref "D5") (pin "A") (pinfunction "A_A") (pintype "passive"))
      (node (ref "D6") (pin "A") (pinfunction "A_A") (pintype "passive"))
      (node (ref "GPS") (pin "S1") (pinfunction "SHIELD_S1") (pintype "bidirectional"))
      (node (ref "GPS") (pin "S2") (pinfunction "SHIELD_S2") (pintype "bidirectional"))
      (node (ref "GPS") (pin "S3") (pinfunction "SHIELD_S3") (pintype "bidirectional"))
      (node (ref "GPS") (pin "S4") (pinfunction "SHIELD_S4") (pintype "bidirectional"))
      (node (ref "IC1") (pin "20") (pinfunction "VSSA/VREF-_20") (pintype "bidirectional"))
      (node (ref "IC1") (pin "49") (pinfunction "VSS_49") (pintype "bidirectional"))
      (node (ref "IC1") (pin "74") (pinfunction "VSS_74") (pintype "bidirectional"))
      (node (ref "IC1") (pin "99") (pinfunction "VSS_99") (pintype "bidirectional"))
      (node (ref "IC10") (pin "2") (pinfunction "V-_2") (pintype "power_in"))
      (node (ref "IC11") (pin "4") (pinfunction "GND_4") (pintype "power_in"))
      (node (ref "IC12") (pin "4") (pinfunction "GND_4") (pintype "power_in"))
      (node (ref "IC13") (pin "4") (pinfunction "GND_4") (pintype "power_in"))
      (node (ref "IC14") (pin "4") (pinfunction "GND_4") (pintype "power_in"))
      (node (ref "IC15") (pin "2") (pinfunction "GND_2") (pintype "bidirectional"))
      (node (ref "IC16") (pin "2") (pinfunction "GND_2") (pintype "passive"))
      (node (ref "IC17") (pin "2") (pinfunction "V-_2") (pintype "power_in"))
      (node (ref "IC18") (pin "2") (pinfunction "GND_2") (pintype "bidirectional"))
      (node (ref "IC2") (pin "2") (pinfunction "V-_2") (pintype "power_in"))
      (node (ref "IC3") (pin "1") (pinfunction "GND_1") (pintype "bidirectional"))
      (node (ref "IC3") (pin "10") (pinfunction "GND_10") (pintype "bidirectional"))
      (node (ref "IC3") (pin "12") (pinfunction "GND_12") (pintype "bidirectional"))
      (node (ref "IC4") (pin "2") (pinfunction "V-_2") (pintype "power_in"))
      (node (ref "IC5") (pin "2") (pinfunction "V-_2") (pintype "power_in"))
      (node (ref "IC6") (pin "2") (pinfunction "V-_2") (pintype "power_in"))
      (node (ref "IC7") (pin "2") (pinfunction "V-_2") (pintype "power_in"))
      (node (ref "IC8") (pin "2") (pinfunction "V-_2") (pintype "power_in"))
      (node (ref "IC9") (pin "2") (pinfunction "V-_2") (pintype "power_in"))
      (node (ref "Q2") (pin "2") (pinfunction "S_2") (pintype "passive"))
      (node (ref "R37") (pin "1") (pinfunction "1_1") (pintype "passive"))
      (node (ref "R40") (pin "1") (pinfunction "1_1") (pintype "passive"))
      (node (ref "R42") (pin "1") (pinfunction "1_1") (pintype "passive"))
      (node (ref "X5") (pin "GND1") (pinfunction "GND_GND1") (pintype "bidirectional"))
      (node (ref "X5") (pin "GND2") (pinfunction "GND_GND2") (pintype "bidirectional"))
      (node (ref "X5") (pin "GND3") (pinfunction "GND_GND3") (pintype "bidirectional"))
      (node (ref "X5") (pin "H1") (pinfunction "GND_H1") (pintype "bidirectional"))
      (node (ref "X5") (pin "H2") (pinfunction "GND_H2") (pintype "bidirectional"))
      (node (ref "X5") (pin "H3") (pinfunction "GND_H3") (pintype "bidirectional"))
      (node (ref "X5") (pin "H4") (pinfunction "GND_H4") (pintype "bidirectional"))
      (node (ref "X6") (pin "GND1") (pinfunction "GND_GND1") (pintype "bidirectional"))
      (node (ref "X6") (pin "GND2") (pinfunction "GND_GND2") (pintype "bidirectional"))
      (node (ref "X6") (pin "GND3") (pinfunction "GND_GND3") (pintype "bidirectional"))
      (node (ref "X6") (pin "H1") (pinfunction "GND_H1") (pintype "bidirectional"))
      (node (ref "X6") (pin "H2") (pinfunction "GND_H2") (pintype "bidirectional"))
      (node (ref "X6") (pin "H3") (pinfunction "GND_H3") (pintype "bidirectional"))
      (node (ref "X6") (pin "H4") (pinfunction "GND_H4") (pintype "bidirectional"))
      (node (ref "X8") (pin "GND1") (pinfunction "GND_GND1") (pintype "bidirectional"))
      (node (ref "X8") (pin "GND2") (pinfunction "GND_GND2") (pintype "bidirectional"))
      (node (ref "X8") (pin "GND_DETECT") (pinfunction "GND_GND_DETECT") (pintype "bidirectional"))
      (node (ref "X9") (pin "4") (pinfunction "4_4") (pintype "passive"))
      (node (ref "XO1") (pin "2") (pinfunction "GND_2") (pintype "bidirectional"))
    )
    (net (code "19") (name "GPS_1PPS") (class "Default")
      (node (ref "IC1") (pin "24") (pinfunction "PA1_24") (pintype "bidirectional"))
      (node (ref "IC3") (pin "4") (pinfunction "1PPS_4") (pintype "bidirectional"))
    )
    (net (code "20") (name "GPS_FORCE_ON") (class "Default")
      (node (ref "IC1") (pin "57") (pinfunction "PD10_57") (pintype "bidirectional"))
      (node (ref "IC3") (pin "18") (pinfunction "FORCE_ON_18") (pintype "bidirectional"))
    )
    (net (code "21") (name "I2C3_SCL") (class "Default")
      (node (ref "IC1") (pin "67") (pinfunction "PA8_67") (pintype "bidirectional"))
      (node (ref "X5") (pin "SCL") (pinfunction "SCL_SCL") (pintype "bidirectional"))
      (node (ref "X6") (pin "SCL") (pinfunction "SCL_SCL") (pintype "bidirectional"))
    )
    (net (code "22") (name "I2C3_SDA") (class "Default")
      (node (ref "IC1") (pin "66") (pinfunction "PC9_66") (pintype "bidirectional"))
      (node (ref "X5") (pin "SDA") (pinfunction "SDA_SDA") (pintype "bidirectional"))
      (node (ref "X6") (pin "SDA") (pinfunction "SDA_SDA") (pintype "bidirectional"))
    )
    (net (code "23") (name "NRST") (class "Default")
      (node (ref "C33") (pin "1") (pinfunction "1_1") (pintype "passive"))
      (node (ref "IC1") (pin "14") (pinfunction "NRST_14") (pintype "bidirectional"))
      (node (ref "R36") (pin "1") (pinfunction "1_1") (pintype "passive"))
      (node (ref "X8") (pin "NRESET") (pinfunction "NRESET_NRESET") (pintype "bidirectional"))
    )
    (net (code "24") (name "Net-(C1-Pad2)") (class "Default")
      (node (ref "C1") (pin "2") (pinfunction "2_2") (pintype "passive"))
      (node (ref "R1") (pin "1") (pinfunction "1_1") (pintype "passive"))
      (node (ref "R11") (pin "1") (pinfunction "1_1") (pintype "passive"))
    )
    (net (code "25") (name "Net-(C3-Pad1)") (class "Default")
      (node (ref "C3") (pin "1") (pinfunction "1_1") (pintype "passive"))
      (node (ref "R5") (pin "2") (pinfunction "2_2") (pintype "passive"))
      (node (ref "R6") (pin "1") (pinfunction "1_1") (pintype "passive"))
    )
    (net (code "26") (name "Net-(C4-Pad1)") (class "Default")
      (node (ref "C4") (pin "1") (pinfunction "1_1") (pintype "passive"))
      (node (ref "R4") (pin "2") (pinfunction "2_2") (pintype "passive"))
      (node (ref "R5") (pin "1") (pinfunction "1_1") (pintype "passive"))
    )
    (net (code "27") (name "Net-(C9-Pad1)") (class "Default")
      (node (ref "C9") (pin "1") (pinfunction "1_1") (pintype "passive"))
      (node (ref "R2") (pin "1") (pinfunction "1_1") (pintype "passive"))
    )
    (net (code "28") (name "Net-(C10-Pad2)") (class "Default")
      (node (ref "C10") (pin "2") (pinfunction "2_2") (pintype "passive"))
      (node (ref "R16") (pin "1") (pinfunction "1_1") (pintype "passive"))
      (node (ref "R19") (pin "1") (pinfunction "1_1") (pintype "passive"))
    )
    (net (code "29") (name "Net-(C11-Pad1)") (class "Default")
      (node (ref "C11") (pin "1") (pinfunction "1_1") (pintype "passive"))
      (node (ref "R14") (pin "2") (pinfunction "2_2") (pintype "passive"))
      (node (ref "R15") (pin "1") (pinfunction "1_1") (pintype "passive"))
    )
    (net (code "30") (name "Net-(C12-Pad1)") (class "Default")
      (node (ref "C12") (pin "1") (pinfunction "1_1") (pintype "passive"))
      (node (ref "R13") (pin "2") (pinfunction "2_2") (pintype "passive"))
      (node (ref "R14") (pin "1") (pinfunction "1_1") (pintype "passive"))
    )
    (net (code "31") (name "Net-(C14-Pad1)") (class "Default")
      (node (ref "C14") (pin "1") (pinfunction "1_1") (pintype "passive"))
      (node (ref "R12") (pin "1") (pinfunction "1_1") (pintype "passive"))
    )
    (net (code "32") (name "Net-(C15-Pad2)") (class "Default")
      (node (ref "C15") (pin "2") (pinfunction "2_2") (pintype "passive"))
      (node (ref "R24") (pin "1") (pinfunction "1_1") (pintype "passive"))
      (node (ref "R27") (pin "1") (pinfunction "1_1") (pintype "passive"))
    )
    (net (code "33") (name "Net-(C16-Pad1)") (class "Default")
      (node (ref "C16") (pin "1") (pinfunction "1_1") (pintype "passive"))
      (node (ref "R22") (pin "2") (pinfunction "2_2") (pintype "passive"))
      (node (ref "R23") (pin "1") (pinfunction "1_1") (pintype "passive"))
    )
    (net (code "34") (name "Net-(C17-Pad1)") (class "Default")
      (node (ref "C17") (pin "1") (pinfunction "1_1") (pintype "passive"))
      (node (ref "R21") (pin "2") (pinfunction "2_2") (pintype "passive"))
      (node (ref "R22") (pin "1") (pinfunction "1_1") (pintype "passive"))
    )
    (net (code "35") (name "Net-(C19-Pad1)") (class "Default")
      (node (ref "C19") (pin "1") (pinfunction "1_1") (pintype "passive"))
      (node (ref "R20") (pin "1") (pinfunction "1_1") (pintype "passive"))
    )
    (net (code "36") (name "Net-(C20-Pad2)") (class "Default")
      (node (ref "C20") (pin "2") (pinfunction "2_2") (pintype "passive"))
      (node (ref "R32") (pin "1") (pinfunction "1_1") (pintype "passive"))
      (node (ref "R35") (pin "1") (pinfunction "1_1") (pintype "passive"))
    )
    (net (code "37") (name "Net-(C21-Pad1)") (class "Default")
      (node (ref "C21") (pin "1") (pinfunction "1_1") (pintype "passive"))
      (node (ref "R30") (pin "2") (pinfunction "2_2") (pintype "passive"))
      (node (ref "R31") (pin "1") (pinfunction "1_1") (pintype "passive"))
    )
    (net (code "38") (name "Net-(C22-Pad1)") (class "Default")
      (node (ref "C22") (pin "1") (pinfunction "1_1") (pintype "passive"))
      (node (ref "R29") (pin "2") (pinfunction "2_2") (pintype "passive"))
      (node (ref "R30") (pin "1") (pinfunction "1_1") (pintype "passive"))
    )
    (net (code "39") (name "Net-(C24-Pad1)") (class "Default")
      (node (ref "C24") (pin "1") (pinfunction "1_1") (pintype "passive"))
      (node (ref "R28") (pin "1") (pinfunction "1_1") (pintype "passive"))
    )
    (net (code "40") (name "Net-(CH1-CENTER)") (class "Default")
      (node (ref "C1") (pin "1") (pinfunction "1_1") (pintype "passive"))
      (node (ref "CH1") (pin "C") (pinfunction "CENTER_C") (pintype "bidirectional"))
      (node (ref "D3") (pin "C") (pinfunction "C_C") (pintype "passive"))
      (node (ref "L1") (pin "2") (pinfunction "2_2") (pintype "passive"))
      (node (ref "R2") (pin "2") (pinfunction "2_2") (pintype "passive"))
    )
    (net (code "41") (name "Net-(CH2-CENTER)") (class "Default")
      (node (ref "C10") (pin "1") (pinfunction "1_1") (pintype "passive"))
      (node (ref "CH2") (pin "C") (pinfunction "CENTER_C") (pintype "bidirectional"))
      (node (ref "D1") (pin "C") (pinfunction "C_C") (pintype "passive"))
      (node (ref "L3") (pin "2") (pinfunction "2_2") (pintype "passive"))
      (node (ref "R12") (pin "2") (pinfunction "2_2") (pintype "passive"))
    )
    (net (code "42") (name "Net-(CH3-CENTER)") (class "Default")
      (node (ref "C15") (pin "1") (pinfunction "1_1") (pintype "passive"))
      (node (ref "CH3") (pin "C") (pinfunction "CENTER_C") (pintype "bidirectional"))
      (node (ref "D2") (pin "C") (pinfunction "C_C") (pintype "passive"))
      (node (ref "L4") (pin "2") (pinfunction "2_2") (pintype "passive"))
      (node (ref "R20") (pin "2") (pinfunction "2_2") (pintype "passive"))
    )
    (net (code "43") (name "Net-(CH4-CENTER)") (class "Default")
      (node (ref "C20") (pin "1") (pinfunction "1_1") (pintype "passive"))
      (node (ref "CH4") (pin "C") (pinfunction "CENTER_C") (pintype "bidirectional"))
      (node (ref "D5") (pin "C") (pinfunction "C_C") (pintype "passive"))
      (node (ref "L5") (pin "2") (pinfunction "2_2") (pintype "passive"))
      (node (ref "R28") (pin "2") (pinfunction "2_2") (pintype "passive"))
    )
    (net (code "44") (name "Net-(GPS-CENTER)") (class "Default")
      (node (ref "C2") (pin "1") (pinfunction "1_1") (pintype "passive"))
      (node (ref "D4") (pin "C") (pinfunction "C_C") (pintype "passive"))
      (node (ref "GPS") (pin "C") (pinfunction "CENTER_C") (pintype "bidirectional"))
      (node (ref "L2") (pin "1") (pinfunction "1_1") (pintype "passive"))
      (node (ref "R8") (pin "1") (pinfunction "1_1") (pintype "passive"))
    )
    (net (code "45") (name "Net-(IC1-BOOT0)") (class "Default")
      (node (ref "IC1") (pin "94") (pinfunction "BOOT0_94") (pintype "bidirectional"))
      (node (ref "R37") (pin "2") (pinfunction "2_2") (pintype "passive"))
    )
    (net (code "46") (name "Net-(IC1-PF0{slash}OSC_IN)") (class "Default")
      (node (ref "C34") (pin "2") (pinfunction "2_2") (pintype "passive"))
      (node (ref "IC1") (pin "12") (pinfunction "PF0/OSC_IN_12") (pintype "bidirectional"))
      (node (ref "R38") (pin "1") (pinfunction "1_1") (pintype "passive"))
    )
    (net (code "47") (name "Net-(IC1-PF1{slash}OSC_OUT)") (class "Default")
      (node (ref "IC1") (pin "13") (pinfunction "PF1/OSC_OUT_13") (pintype "bidirectional"))
      (node (ref "R38") (pin "2") (pinfunction "2_2") (pintype "passive"))
    )
    (net (code "48") (name "Net-(IC2-+IN)") (class "Default")
      (node (ref "C5") (pin "1") (pinfunction "1_1") (pintype "passive"))
      (node (ref "IC2") (pin "3") (pinfunction "+IN_3") (pintype "input"))
      (node (ref "R6") (pin "2") (pinfunction "2_2") (pintype "passive"))
    )
    (net (code "49") (name "Net-(IC3-ANTON)") (class "Default")
      (node (ref "IC3") (pin "13") (pinfunction "ANTON_13") (pintype "bidirectional"))
      (node (ref "Q2") (pin "1") (pinfunction "G_1") (pintype "passive"))
    )
    (net (code "50") (name "Net-(IC3-RF_IN)") (class "Default")
      (node (ref "C6") (pin "1") (pinfunction "1_1") (pintype "passive"))
      (node (ref "IC3") (pin "11") (pinfunction "RF_IN_11") (pintype "bidirectional"))
      (node (ref "R8") (pin "2") (pinfunction "2_2") (pintype "passive"))
    )
    (net (code "51") (name "Net-(IC3-VCC_RF)") (class "Default")
      (node (ref "IC3") (pin "14") (pinfunction "VCC_RF_14") (pintype "bidirectional"))
      (node (ref "Q1") (pin "2") (pinfunction "S_2") (pintype "passive"))
      (node (ref "R10") (pin "2") (pinfunction "2_2") (pintype "passive"))
    )
    (net (code "52") (name "Net-(IC4-+IN)") (class "Default")
      (node (ref "IC4") (pin "3") (pinfunction "+IN_3") (pintype "input"))
      (node (ref "R1") (pin "2") (pinfunction "2_2") (pintype "passive"))
    )
    (net (code "53") (name "Net-(IC4--IN)") (class "Default")
      (node (ref "IC4") (pin "4") (pinfunction "-IN_4") (pintype "input"))
      (node (ref "R3") (pin "1") (pinfunction "1_1") (pintype "passive"))
      (node (ref "R7") (pin "1") (pinfunction "1_1") (pintype "passive"))
    )
    (net (code "54") (name "Net-(IC5-+IN)") (class "Default")
      (node (ref "IC5") (pin "3") (pinfunction "+IN_3") (pintype "input"))
      (node (ref "R16") (pin "2") (pinfunction "2_2") (pintype "passive"))
    )
    (net (code "55") (name "Net-(IC5--IN)") (class "Default")
      (node (ref "IC5") (pin "4") (pinfunction "-IN_4") (pintype "input"))
      (node (ref "R17") (pin "1") (pinfunction "1_1") (pintype "passive"))
      (node (ref "R18") (pin "1") (pinfunction "1_1") (pintype "passive"))
    )
    (net (code "56") (name "Net-(IC6-+IN)") (class "Default")
      (node (ref "C13") (pin "1") (pinfunction "1_1") (pintype "passive"))
      (node (ref "IC6") (pin "3") (pinfunction "+IN_3") (pintype "input"))
      (node (ref "R15") (pin "2") (pinfunction "2_2") (pintype "passive"))
    )
    (net (code "57") (name "Net-(IC7-+IN)") (class "Default")
      (node (ref "IC7") (pin "3") (pinfunction "+IN_3") (pintype "input"))
      (node (ref "R24") (pin "2") (pinfunction "2_2") (pintype "passive"))
    )
    (net (code "58") (name "Net-(IC7--IN)") (class "Default")
      (node (ref "IC7") (pin "4") (pinfunction "-IN_4") (pintype "input"))
      (node (ref "R25") (pin "1") (pinfunction "1_1") (pintype "passive"))
      (node (ref "R26") (pin "1") (pinfunction "1_1") (pintype "passive"))
    )
    (net (code "59") (name "Net-(IC8-+IN)") (class "Default")
      (node (ref "C18") (pin "1") (pinfunction "1_1") (pintype "passive"))
      (node (ref "IC8") (pin "3") (pinfunction "+IN_3") (pintype "input"))
      (node (ref "R23") (pin "2") (pinfunction "2_2") (pintype "passive"))
    )
    (net (code "60") (name "Net-(IC9-+IN)") (class "Default")
      (node (ref "IC9") (pin "3") (pinfunction "+IN_3") (pintype "input"))
      (node (ref "R32") (pin "2") (pinfunction "2_2") (pintype "passive"))
    )
    (net (code "61") (name "Net-(IC9--IN)") (class "Default")
      (node (ref "IC9") (pin "4") (pinfunction "-IN_4") (pintype "input"))
      (node (ref "R33") (pin "1") (pinfunction "1_1") (pintype "passive"))
      (node (ref "R34") (pin "1") (pinfunction "1_1") (pintype "passive"))
    )
    (net (code "62") (name "Net-(IC10-+IN)") (class "Default")
      (node (ref "C23") (pin "1") (pinfunction "1_1") (pintype "passive"))
      (node (ref "IC10") (pin "3") (pinfunction "+IN_3") (pintype "input"))
      (node (ref "R31") (pin "2") (pinfunction "2_2") (pintype "passive"))
    )
    (net (code "63") (name "Net-(IC15-EN)") (class "Default")
      (node (ref "C52") (pin "1") (pinfunction "1_1") (pintype "passive"))
      (node (ref "C54") (pin "+") (pinfunction "+_+") (pintype "passive"))
      (node (ref "C55") (pin "+") (pinfunction "+_+") (pintype "passive"))
      (node (ref "D6") (pin "C") (pinfunction "C_C") (pintype "passive"))
      (node (ref "IC15") (pin "1") (pinfunction "VIN_1") (pintype "bidirectional"))
      (node (ref "IC15") (pin "3") (pinfunction "EN_3") (pintype "bidirectional"))
      (node (ref "PTC1") (pin "2") (pinfunction "2_2") (pintype "passive"))
    )
    (net (code "64") (name "Net-(IC15-FB)") (class "Default")
      (node (ref "C51") (pin "2") (pinfunction "2_2") (pintype "passive"))
      (node (ref "C53") (pin "1") (pinfunction "1_1") (pintype "passive"))
      (node (ref "IC15") (pin "4") (pinfunction "FB_4") (pintype "bidirectional"))
      (node (ref "R39") (pin "1") (pinfunction "1_1") (pintype "passive"))
      (node (ref "R40") (pin "2") (pinfunction "2_2") (pintype "passive"))
    )
    (net (code "65") (name "Net-(IC15-SW)") (class "Default")
      (node (ref "IC15") (pin "5") (pinfunction "SW_5") (pintype "bidirectional"))
      (node (ref "L6") (pin "1") (pinfunction "1_1") (pintype "passive"))
    )
    (net (code "66") (name "Net-(IC16-CB)") (class "Default")
      (node (ref "C58") (pin "1") (pinfunction "1_1") (pintype "passive"))
      (node (ref "IC16") (pin "4") (pinfunction "CB_4") (pintype "input"))
    )
    (net (code "67") (name "Net-(IC16-CE)") (class "Default")
      (node (ref "C57") (pin "1") (pinfunction "1_1") (pintype "passive"))
      (node (ref "IC16") (pin "1") (pinfunction "VIN_1") (pintype "input"))
      (node (ref "IC16") (pin "3") (pinfunction "CE_3") (pintype "input"))
      (node (ref "L7") (pin "1") (pinfunction "1_1") (pintype "passive"))
    )
    (net (code "68") (name "Net-(IC17-+IN)") (class "Default")
      (node (ref "C60") (pin "1") (pinfunction "1_1") (pintype "passive"))
      (node (ref "IC17") (pin "3") (pinfunction "+IN_3") (pintype "input"))
      (node (ref "R41") (pin "1") (pinfunction "1_1") (pintype "passive"))
      (node (ref "R42") (pin "2") (pinfunction "2_2") (pintype "passive"))
    )
    (net (code "69") (name "Net-(L2-Pad2)") (class "Default")
      (node (ref "L2") (pin "2") (pinfunction "2_2") (pintype "passive"))
      (node (ref "R9") (pin "1") (pinfunction "1_1") (pintype "passive"))
    )
    (net (code "70") (name "Net-(Q1-D)") (class "Default")
      (node (ref "Q1") (pin "3") (pinfunction "D_3") (pintype "passive"))
      (node (ref "R9") (pin "2") (pinfunction "2_2") (pintype "passive"))
    )
    (net (code "71") (name "Net-(Q1-G)") (class "Default")
      (node (ref "Q1") (pin "1") (pinfunction "G_1") (pintype "passive"))
      (node (ref "Q2") (pin "3") (pinfunction "D_3") (pintype "passive"))
      (node (ref "R10") (pin "1") (pinfunction "1_1") (pintype "passive"))
    )
    (net (code "72") (name "Net-(XO1-OUT)") (class "Default")
      (node (ref "C34") (pin "1") (pinfunction "1_1") (pintype "passive"))
      (node (ref "XO1") (pin "3") (pinfunction "OUT_3") (pintype "bidirectional"))
    )
    (net (code "73") (name "Net-(XO1-VC)") (class "Default")
      (node (ref "R43") (pin "2") (pinfunction "2_2") (pintype "passive"))
      (node (ref "XO1") (pin "1") (pinfunction "VC_1") (pintype "bidirectional"))
    )
    (net (code "74") (name "Net-(XO1-VCC)") (class "Default")
      (node (ref "C61") (pin "1") (pinfunction "1_1") (pintype "passive"))
      (node (ref "C62") (pin "1") (pinfunction "1_1") (pintype "passive"))
      (node (ref "L8") (pin "1") (pinfunction "1_1") (pintype "passive"))
      (node (ref "XO1") (pin "4") (pinfunction "VCC_4") (pintype "bidirectional"))
    )
    (net (code "75") (name "SPI1_MISO_MOSI") (class "Default")
      (node (ref "IC1") (pin "90") (pinfunction "PB4_90") (pintype "bidirectional"))
      (node (ref "IC1") (pin "91") (pinfunction "PB5_91") (pintype "bidirectional"))
      (node (ref "X5") (pin "DATA") (pinfunction "DATA_DATA") (pintype "bidirectional"))
      (node (ref "X6") (pin "DATA") (pinfunction "DATA_DATA") (pintype "bidirectional"))
    )
    (net (code "76") (name "SPI1_NSS") (class "Default")
      (node (ref "IC1") (pin "77") (pinfunction "PA15_77") (pintype "bidirectional"))
      (node (ref "X5") (pin "FRAME") (pinfunction "FRAME_FRAME") (pintype "bidirectional"))
      (node (ref "X6") (pin "FRAME") (pinfunction "FRAME_FRAME") (pintype "bidirectional"))
    )
    (net (code "77") (name "SPI1_SCK") (class "Default")
      (node (ref "IC1") (pin "89") (pinfunction "PB3_89") (pintype "bidirectional"))
      (node (ref "X5") (pin "CLK") (pinfunction "CLK_CLK") (pintype "bidirectional"))
      (node (ref "X6") (pin "CLK") (pinfunction "CLK_CLK") (pintype "bidirectional"))
    )
    (net (code "78") (name "SPI4_MISO") (class "Default")
      (node (ref "IC1") (pin "4") (pinfunction "PE5_4") (pintype "bidirectional"))
      (node (ref "IC11") (pin "2") (pinfunction "SO_2") (pintype "bidirectional"))
      (node (ref "IC12") (pin "2") (pinfunction "SO_2") (pintype "bidirectional"))
      (node (ref "IC13") (pin "2") (pinfunction "SO_2") (pintype "bidirectional"))
      (node (ref "IC14") (pin "2") (pinfunction "SO_2") (pintype "bidirectional"))
    )
    (net (code "79") (name "SPI4_MOSI") (class "Default")
      (node (ref "IC1") (pin "5") (pinfunction "PE6_5") (pintype "bidirectional"))
      (node (ref "IC11") (pin "5") (pinfunction "SI_5") (pintype "input"))
      (node (ref "IC12") (pin "5") (pinfunction "SI_5") (pintype "input"))
      (node (ref "IC13") (pin "5") (pinfunction "SI_5") (pintype "input"))
      (node (ref "IC14") (pin "5") (pinfunction "SI_5") (pintype "input"))
    )
    (net (code "80") (name "SPI4_SCK") (class "Default")
      (node (ref "IC1") (pin "1") (pinfunction "PE2_1") (pintype "bidirectional"))
      (node (ref "IC11") (pin "6") (pinfunction "SCK_6") (pintype "input"))
      (node (ref "IC12") (pin "6") (pinfunction "SCK_6") (pintype "input"))
      (node (ref "IC13") (pin "6") (pinfunction "SCK_6") (pintype "input"))
      (node (ref "IC14") (pin "6") (pinfunction "SCK_6") (pintype "input"))
    )
    (net (code "81") (name "SRAM1_CS") (class "Default")
      (node (ref "IC1") (pin "92") (pinfunction "PB6_92") (pintype "bidirectional"))
      (node (ref "IC11") (pin "1") (pinfunction "~{CS}_1") (pintype "input"))
    )
    (net (code "82") (name "SRAM2_CS") (class "Default")
      (node (ref "IC1") (pin "93") (pinfunction "PB7_93") (pintype "bidirectional"))
      (node (ref "IC12") (pin "1") (pinfunction "~{CS}_1") (pintype "input"))
    )
    (net (code "83") (name "SRAM3_CS") (class "Default")
      (node (ref "IC1") (pin "95") (pinfunction "PB8_95") (pintype "bidirectional"))
      (node (ref "IC13") (pin "1") (pinfunction "~{CS}_1") (pintype "input"))
    )
    (net (code "84") (name "SRAM4_CS") (class "Default")
      (node (ref "IC1") (pin "96") (pinfunction "PB9_96") (pintype "bidirectional"))
      (node (ref "IC14") (pin "1") (pinfunction "~{CS}_1") (pintype "input"))
    )
    (net (code "85") (name "SWCLK") (class "Default")
      (node (ref "IC1") (pin "76") (pinfunction "PA14_76") (pintype "bidirectional"))
      (node (ref "X8") (pin "SWCLK/TCK") (pinfunction "SWCLK/TCK_SWCLK/TCK") (pintype "bidirectional"))
    )
    (net (code "86") (name "SWDIO") (class "Default")
      (node (ref "IC1") (pin "72") (pinfunction "PA13_72") (pintype "bidirectional"))
      (node (ref "X8") (pin "SWDIO/TMS") (pinfunction "SWDIO/TMS_SWDIO/TMS") (pintype "bidirectional"))
    )
    (net (code "87") (name "USART1_RX") (class "Default")
      (node (ref "IC1") (pin "69") (pinfunction "PA10_69") (pintype "bidirectional"))
      (node (ref "X9") (pin "3") (pinfunction "3_3") (pintype "passive"))
    )
    (net (code "88") (name "USART1_TX") (class "Default")
      (node (ref "IC1") (pin "68") (pinfunction "PA9_68") (pintype "bidirectional"))
      (node (ref "X9") (pin "2") (pinfunction "2_2") (pintype "passive"))
    )
    (net (code "89") (name "USART3_RX") (class "Default")
      (node (ref "IC1") (pin "56") (pinfunction "PD9_56") (pintype "bidirectional"))
      (node (ref "IC3") (pin "2") (pinfunction "TXD1_2") (pintype "bidirectional"))
    )
    (net (code "90") (name "USART3_TX") (class "Default")
      (node (ref "IC1") (pin "55") (pinfunction "PD8_55") (pintype "bidirectional"))
      (node (ref "IC3") (pin "3") (pinfunction "RXD1_3") (pintype "bidirectional"))
    )
    (net (code "91") (name "UXB_ID") (class "Default")
      (node (ref "IC1") (pin "78") (pinfunction "PC10_78") (pintype "bidirectional"))
      (node (ref "X5") (pin "ID") (pinfunction "ID_ID") (pintype "bidirectional"))
      (node (ref "X6") (pin "ID") (pinfunction "ID_ID") (pintype "bidirectional"))
    )
    (net (code "92") (name "UXB_IRQ") (class "Default")
      (node (ref "IC1") (pin "80") (pinfunction "PC12_80") (pintype "bidirectional"))
      (node (ref "X5") (pin "IRQ") (pinfunction "IRQ_IRQ") (pintype "bidirectional"))
      (node (ref "X6") (pin "IRQ") (pinfunction "IRQ_IRQ") (pintype "bidirectional"))
    )
    (net (code "93") (name "UXB_WAKEUP") (class "Default")
      (node (ref "IC1") (pin "79") (pinfunction "PC11_79") (pintype "bidirectional"))
      (node (ref "X5") (pin "WAKEUP") (pinfunction "WAKEUP_WAKEUP") (pintype "bidirectional"))
      (node (ref "X6") (pin "WAKEUP") (pinfunction "WAKEUP_WAKEUP") (pintype "bidirectional"))
    )
    (net (code "94") (name "VCC") (class "Default")
      (node (ref "C29") (pin "1") (pinfunction "1_1") (pintype "passive"))
      (node (ref "C30") (pin "1") (pinfunction "1_1") (pintype "passive"))
      (node (ref "C31") (pin "1") (pinfunction "1_1") (pintype "passive"))
      (node (ref "C32") (pin "1") (pinfunction "1_1") (pintype "passive"))
      (node (ref "C35") (pin "1") (pinfunction "1_1") (pintype "passive"))
      (node (ref "C36") (pin "1") (pinfunction "1_1") (pintype "passive"))
      (node (ref "C37") (pin "1") (pinfunction "1_1") (pintype "passive"))
      (node (ref "C38") (pin "1") (pinfunction "1_1") (pintype "passive"))
      (node (ref "C39") (pin "1") (pinfunction "1_1") (pintype "passive"))
      (node (ref "C40") (pin "1") (pinfunction "1_1") (pintype "passive"))
      (node (ref "C41") (pin "1") (pinfunction "1_1") (pintype "passive"))
      (node (ref "C42") (pin "1") (pinfunction "1_1") (pintype "passive"))
      (node (ref "C49") (pin "1") (pinfunction "1_1") (pintype "passive"))
      (node (ref "C50") (pin "1") (pinfunction "1_1") (pintype "passive"))
      (node (ref "C51") (pin "1") (pinfunction "1_1") (pintype "passive"))
      (node (ref "C7") (pin "1") (pinfunction "1_1") (pintype "passive"))
      (node (ref "C8") (pin "1") (pinfunction "1_1") (pintype "passive"))
      (node (ref "IC1") (pin "100") (pinfunction "VDD_100") (pintype "bidirectional"))
      (node (ref "IC1") (pin "28") (pinfunction "VDD_28") (pintype "bidirectional"))
      (node (ref "IC1") (pin "50") (pinfunction "VDD_50") (pintype "bidirectional"))
      (node (ref "IC1") (pin "6") (pinfunction "VBAT_6") (pintype "bidirectional"))
      (node (ref "IC1") (pin "75") (pinfunction "VDD_75") (pintype "bidirectional"))
      (node (ref "IC11") (pin "8") (pinfunction "VCC_8") (pintype "power_in"))
      (node (ref "IC12") (pin "8") (pinfunction "VCC_8") (pintype "power_in"))
      (node (ref "IC13") (pin "8") (pinfunction "VCC_8") (pintype "power_in"))
      (node (ref "IC14") (pin "8") (pinfunction "VCC_8") (pintype "power_in"))
      (node (ref "IC3") (pin "6") (pinfunction "V_BCKP_6") (pintype "bidirectional"))
      (node (ref "IC3") (pin "8") (pinfunction "VCC_8") (pintype "bidirectional"))
      (node (ref "L6") (pin "2") (pinfunction "2_2") (pintype "passive"))
      (node (ref "L8") (pin "2") (pinfunction "2_2") (pintype "passive"))
      (node (ref "R36") (pin "2") (pinfunction "2_2") (pintype "passive"))
      (node (ref "R39") (pin "2") (pinfunction "2_2") (pintype "passive"))
      (node (ref "X8") (pin "VCC") (pinfunction "VCC_VCC") (pintype "bidirectional"))
    )
    (net (code "95") (name "VDDA") (class "Default")
      (node (ref "C25") (pin "1") (pinfunction "1_1") (pintype "passive"))
      (node (ref "C26") (pin "1") (pinfunction "1_1") (pintype "passive"))
      (node (ref "C27") (pin "1") (pinfunction "1_1") (pintype "passive"))
      (node (ref "C28") (pin "1") (pinfunction "1_1") (pintype "passive"))
      (node (ref "C43") (pin "1") (pinfunction "1_1") (pintype "passive"))
      (node (ref "C44") (pin "1") (pinfunction "1_1") (pintype "passive"))
      (node (ref "C45") (pin "1") (pinfunction "1_1") (pintype "passive"))
      (node (ref "C59") (pin "1") (pinfunction "1_1") (pintype "passive"))
      (node (ref "IC1") (pin "22") (pinfunction "VDDA_22") (pintype "bidirectional"))
      (node (ref "IC10") (pin "5") (pinfunction "V+_5") (pintype "power_in"))
      (node (ref "IC16") (pin "5") (pinfunction "VOUT_5") (pintype "passive"))
      (node (ref "IC17") (pin "5") (pinfunction "V+_5") (pintype "power_in"))
      (node (ref "IC18") (pin "3") (pinfunction "VIN_3") (pintype "bidirectional"))
      (node (ref "IC2") (pin "5") (pinfunction "V+_5") (pintype "power_in"))
      (node (ref "IC4") (pin "5") (pinfunction "V+_5") (pintype "power_in"))
      (node (ref "IC5") (pin "5") (pinfunction "V+_5") (pintype "power_in"))
      (node (ref "IC6") (pin "5") (pinfunction "V+_5") (pintype "power_in"))
      (node (ref "IC7") (pin "5") (pinfunction "V+_5") (pintype "power_in"))
      (node (ref "IC8") (pin "5") (pinfunction "V+_5") (pintype "power_in"))
      (node (ref "IC9") (pin "5") (pinfunction "V+_5") (pintype "power_in"))
      (node (ref "L1") (pin "1") (pinfunction "1_1") (pintype "passive"))
      (node (ref "L3") (pin "1") (pinfunction "1_1") (pintype "passive"))
      (node (ref "L4") (pin "1") (pinfunction "1_1") (pintype "passive"))
      (node (ref "L5") (pin "1") (pinfunction "1_1") (pintype "passive"))
    )
    (net (code "96") (name "VDDA{slash}2") (class "Default")
      (node (ref "IC17") (pin "1") (pinfunction "OUT_1") (pintype "output"))
      (node (ref "IC17") (pin "4") (pinfunction "-IN_4") (pintype "input"))
      (node (ref "R11") (pin "2") (pinfunction "2_2") (pintype "passive"))
      (node (ref "R17") (pin "2") (pinfunction "2_2") (pintype "passive"))
      (node (ref "R19") (pin "2") (pinfunction "2_2") (pintype "passive"))
      (node (ref "R25") (pin "2") (pinfunction "2_2") (pintype "passive"))
      (node (ref "R27") (pin "2") (pinfunction "2_2") (pintype "passive"))
      (node (ref "R3") (pin "2") (pinfunction "2_2") (pintype "passive"))
      (node (ref "R33") (pin "2") (pinfunction "2_2") (pintype "passive"))
      (node (ref "R35") (pin "2") (pinfunction "2_2") (pintype "passive"))
    )
    (net (code "97") (name "VREF") (class "Default")
      (node (ref "C46") (pin "1") (pinfunction "1_1") (pintype "passive"))
      (node (ref "C47") (pin "1") (pinfunction "1_1") (pintype "passive"))
      (node (ref "C48") (pin "1") (pinfunction "1_1") (pintype "passive"))
      (node (ref "IC1") (pin "21") (pinfunction "VREF+_21") (pintype "bidirectional"))
      (node (ref "IC18") (pin "4") (pinfunction "VOUT_4") (pintype "bidirectional"))
      (node (ref "R41") (pin "2") (pinfunction "2_2") (pintype "passive"))
    )
    (net (code "98") (name "unconnected-(IC1-PA5-Pad30)") (class "Default")
      (node (ref "IC1") (pin "30") (pinfunction "PA5_30") (pintype "bidirectional"))
    )
    (net (code "99") (name "unconnected-(IC1-PA11-Pad70)") (class "Default")
      (node (ref "IC1") (pin "70") (pinfunction "PA11_70") (pintype "bidirectional"))
    )
    (net (code "100") (name "unconnected-(IC1-PA12-Pad71)") (class "Default")
      (node (ref "IC1") (pin "71") (pinfunction "PA12_71") (pintype "bidirectional"))
    )
    (net (code "101") (name "unconnected-(IC1-PB0-Pad35)") (class "Default")
      (node (ref "IC1") (pin "35") (pinfunction "PB0_35") (pintype "bidirectional"))
    )
    (net (code "102") (name "unconnected-(IC1-PB2-Pad37)") (class "Default")
      (node (ref "IC1") (pin "37") (pinfunction "PB2_37") (pintype "bidirectional"))
    )
    (net (code "103") (name "unconnected-(IC1-PB10-Pad47)") (class "Default")
      (node (ref "IC1") (pin "47") (pinfunction "PB10_47") (pintype "bidirectional"))
    )
    (net (code "104") (name "unconnected-(IC1-PB11-Pad48)") (class "Default")
      (node (ref "IC1") (pin "48") (pinfunction "PB11_48") (pintype "bidirectional"))
    )
    (net (code "105") (name "unconnected-(IC1-PC0-Pad15)") (class "Default")
      (node (ref "IC1") (pin "15") (pinfunction "PC0_15") (pintype "bidirectional"))
    )
    (net (code "106") (name "unconnected-(IC1-PC1-Pad16)") (class "Default")
      (node (ref "IC1") (pin "16") (pinfunction "PC1_16") (pintype "bidirectional"))
    )
    (net (code "107") (name "unconnected-(IC1-PC2-Pad17)") (class "Default")
      (node (ref "IC1") (pin "17") (pinfunction "PC2_17") (pintype "bidirectional"))
    )
    (net (code "108") (name "unconnected-(IC1-PC3-Pad18)") (class "Default")
      (node (ref "IC1") (pin "18") (pinfunction "PC3_18") (pintype "bidirectional"))
    )
    (net (code "109") (name "unconnected-(IC1-PC5-Pad34)") (class "Default")
      (node (ref "IC1") (pin "34") (pinfunction "PC5_34") (pintype "bidirectional"))
    )
    (net (code "110") (name "unconnected-(IC1-PC6-Pad63)") (class "Default")
      (node (ref "IC1") (pin "63") (pinfunction "PC6_63") (pintype "bidirectional"))
    )
    (net (code "111") (name "unconnected-(IC1-PC7-Pad64)") (class "Default")
      (node (ref "IC1") (pin "64") (pinfunction "PC7_64") (pintype "bidirectional"))
    )
    (net (code "112") (name "unconnected-(IC1-PC8-Pad65)") (class "Default")
      (node (ref "IC1") (pin "65") (pinfunction "PC8_65") (pintype "bidirectional"))
    )
    (net (code "113") (name "unconnected-(IC1-PC13-Pad7)") (class "Default")
      (node (ref "IC1") (pin "7") (pinfunction "PC13_7") (pintype "bidirectional"))
    )
    (net (code "114") (name "unconnected-(IC1-PC14{slash}OSC32_IN-Pad8)") (class "Default")
      (node (ref "IC1") (pin "8") (pinfunction "PC14/OSC32_IN_8") (pintype "bidirectional"))
    )
    (net (code "115") (name "unconnected-(IC1-PC15{slash}OSC32_OUT-Pad9)") (class "Default")
      (node (ref "IC1") (pin "9") (pinfunction "PC15/OSC32_OUT_9") (pintype "bidirectional"))
    )
    (net (code "116") (name "unconnected-(IC1-PD0-Pad81)") (class "Default")
      (node (ref "IC1") (pin "81") (pinfunction "PD0_81") (pintype "bidirectional"))
    )
    (net (code "117") (name "unconnected-(IC1-PD1-Pad82)") (class "Default")
      (node (ref "IC1") (pin "82") (pinfunction "PD1_82") (pintype "bidirectional"))
    )
    (net (code "118") (name "unconnected-(IC1-PD2-Pad83)") (class "Default")
      (node (ref "IC1") (pin "83") (pinfunction "PD2_83") (pintype "bidirectional"))
    )
    (net (code "119") (name "unconnected-(IC1-PD3-Pad84)") (class "Default")
      (node (ref "IC1") (pin "84") (pinfunction "PD3_84") (pintype "bidirectional"))
    )
    (net (code "120") (name "unconnected-(IC1-PD4-Pad85)") (class "Default")
      (node (ref "IC1") (pin "85") (pinfunction "PD4_85") (pintype "bidirectional"))
    )
    (net (code "121") (name "unconnected-(IC1-PD5-Pad86)") (class "Default")
      (node (ref "IC1") (pin "86") (pinfunction "PD5_86") (pintype "bidirectional"))
    )
    (net (code "122") (name "unconnected-(IC1-PD6-Pad87)") (class "Default")
      (node (ref "IC1") (pin "87") (pinfunction "PD6_87") (pintype "bidirectional"))
    )
    (net (code "123") (name "unconnected-(IC1-PD7-Pad88)") (class "Default")
      (node (ref "IC1") (pin "88") (pinfunction "PD7_88") (pintype "bidirectional"))
    )
    (net (code "124") (name "unconnected-(IC1-PD11-Pad58)") (class "Default")
      (node (ref "IC1") (pin "58") (pinfunction "PD11_58") (pintype "bidirectional"))
    )
    (net (code "125") (name "unconnected-(IC1-PD12-Pad59)") (class "Default")
      (node (ref "IC1") (pin "59") (pinfunction "PD12_59") (pintype "bidirectional"))
    )
    (net (code "126") (name "unconnected-(IC1-PD13-Pad60)") (class "Default")
      (node (ref "IC1") (pin "60") (pinfunction "PD13_60") (pintype "bidirectional"))
    )
    (net (code "127") (name "unconnected-(IC1-PD14-Pad61)") (class "Default")
      (node (ref "IC1") (pin "61") (pinfunction "PD14_61") (pintype "bidirectional"))
    )
    (net (code "128") (name "unconnected-(IC1-PD15-Pad62)") (class "Default")
      (node (ref "IC1") (pin "62") (pinfunction "PD15_62") (pintype "bidirectional"))
    )
    (net (code "129") (name "unconnected-(IC1-PE0-Pad97)") (class "Default")
      (node (ref "IC1") (pin "97") (pinfunction "PE0_97") (pintype "bidirectional"))
    )
    (net (code "130") (name "unconnected-(IC1-PE1-Pad98)") (class "Default")
      (node (ref "IC1") (pin "98") (pinfunction "PE1_98") (pintype "bidirectional"))
    )
    (net (code "131") (name "unconnected-(IC1-PE3-Pad2)") (class "Default")
      (node (ref "IC1") (pin "2") (pinfunction "PE3_2") (pintype "bidirectional"))
    )
    (net (code "132") (name "unconnected-(IC1-PE4-Pad3)") (class "Default")
      (node (ref "IC1") (pin "3") (pinfunction "PE4_3") (pintype "bidirectional"))
    )
    (net (code "133") (name "unconnected-(IC1-PE7-Pad38)") (class "Default")
      (node (ref "IC1") (pin "38") (pinfunction "PE7_38") (pintype "bidirectional"))
    )
    (net (code "134") (name "unconnected-(IC1-PE8-Pad39)") (class "Default")
      (node (ref "IC1") (pin "39") (pinfunction "PE8_39") (pintype "bidirectional"))
    )
    (net (code "135") (name "unconnected-(IC1-PE10-Pad41)") (class "Default")
      (node (ref "IC1") (pin "41") (pinfunction "PE10_41") (pintype "bidirectional"))
    )
    (net (code "136") (name "unconnected-(IC1-PE11-Pad42)") (class "Default")
      (node (ref "IC1") (pin "42") (pinfunction "PE11_42") (pintype "bidirectional"))
    )
    (net (code "137") (name "unconnected-(IC1-PE12-Pad43)") (class "Default")
      (node (ref "IC1") (pin "43") (pinfunction "PE12_43") (pintype "bidirectional"))
    )
    (net (code "138") (name "unconnected-(IC1-PF2-Pad19)") (class "Default")
      (node (ref "IC1") (pin "19") (pinfunction "PF2_19") (pintype "bidirectional"))
    )
    (net (code "139") (name "unconnected-(IC1-PF4-Pad27)") (class "Default")
      (node (ref "IC1") (pin "27") (pinfunction "PF4_27") (pintype "bidirectional"))
    )
    (net (code "140") (name "unconnected-(IC1-PF6-Pad73)") (class "Default")
      (node (ref "IC1") (pin "73") (pinfunction "PF6_73") (pintype "bidirectional"))
    )
    (net (code "141") (name "unconnected-(IC1-PF9-Pad10)") (class "Default")
      (node (ref "IC1") (pin "10") (pinfunction "PF9_10") (pintype "bidirectional"))
    )
    (net (code "142") (name "unconnected-(IC1-PF10-Pad11)") (class "Default")
      (node (ref "IC1") (pin "11") (pinfunction "PF10_11") (pintype "bidirectional"))
    )
    (net (code "143") (name "unconnected-(IC3-RESET-Pad9)") (class "Default")
      (node (ref "IC3") (pin "9") (pinfunction "RESET_9") (pintype "bidirectional"))
    )
    (net (code "144") (name "unconnected-(IC3-STANDBY-Pad5)") (class "Default")
      (node (ref "IC3") (pin "5") (pinfunction "STANDBY_5") (pintype "bidirectional"))
    )
    (net (code "145") (name "unconnected-(IC11-~{HOLD}-Pad7)") (class "Default")
      (node (ref "IC11") (pin "7") (pinfunction "~{HOLD}_7") (pintype "input"))
    )
    (net (code "146") (name "unconnected-(IC11-~{WP}-Pad3)") (class "Default")
      (node (ref "IC11") (pin "3") (pinfunction "~{WP}_3") (pintype "input"))
    )
    (net (code "147") (name "unconnected-(IC12-~{HOLD}-Pad7)") (class "Default")
      (node (ref "IC12") (pin "7") (pinfunction "~{HOLD}_7") (pintype "input"))
    )
    (net (code "148") (name "unconnected-(IC12-~{WP}-Pad3)") (class "Default")
      (node (ref "IC12") (pin "3") (pinfunction "~{WP}_3") (pintype "input"))
    )
    (net (code "149") (name "unconnected-(IC13-~{HOLD}-Pad7)") (class "Default")
      (node (ref "IC13") (pin "7") (pinfunction "~{HOLD}_7") (pintype "input"))
    )
    (net (code "150") (name "unconnected-(IC13-~{WP}-Pad3)") (class "Default")
      (node (ref "IC13") (pin "3") (pinfunction "~{WP}_3") (pintype "input"))
    )
    (net (code "151") (name "unconnected-(IC14-~{HOLD}-Pad7)") (class "Default")
      (node (ref "IC14") (pin "7") (pinfunction "~{HOLD}_7") (pintype "input"))
    )
    (net (code "152") (name "unconnected-(IC14-~{WP}-Pad3)") (class "Default")
      (node (ref "IC14") (pin "3") (pinfunction "~{WP}_3") (pintype "input"))
    )
    (net (code "153") (name "unconnected-(IC18-TRIM-Pad5)") (class "Default")
      (node (ref "IC18") (pin "5") (pinfunction "TRIM_5") (pintype "bidirectional"))
    )
    (net (code "154") (name "unconnected-(X8-PadNC{slash}TDI)") (class "Default")
      (node (ref "X8") (pin "NC/TDI") (pinfunction "NC/TDI_NC/TDI") (pintype "bidirectional"))
    )
    (net (code "155") (name "unconnected-(X8-PadSWO{slash}TDO)") (class "Default")
      (node (ref "X8") (pin "SWO/TDO") (pinfunction "SWO/TDO_SWO/TDO") (pintype "bidirectional"))
    )
  )
)
